# io-board-d-5.net
KiCad netlist of a schematic drawn in EAGLE
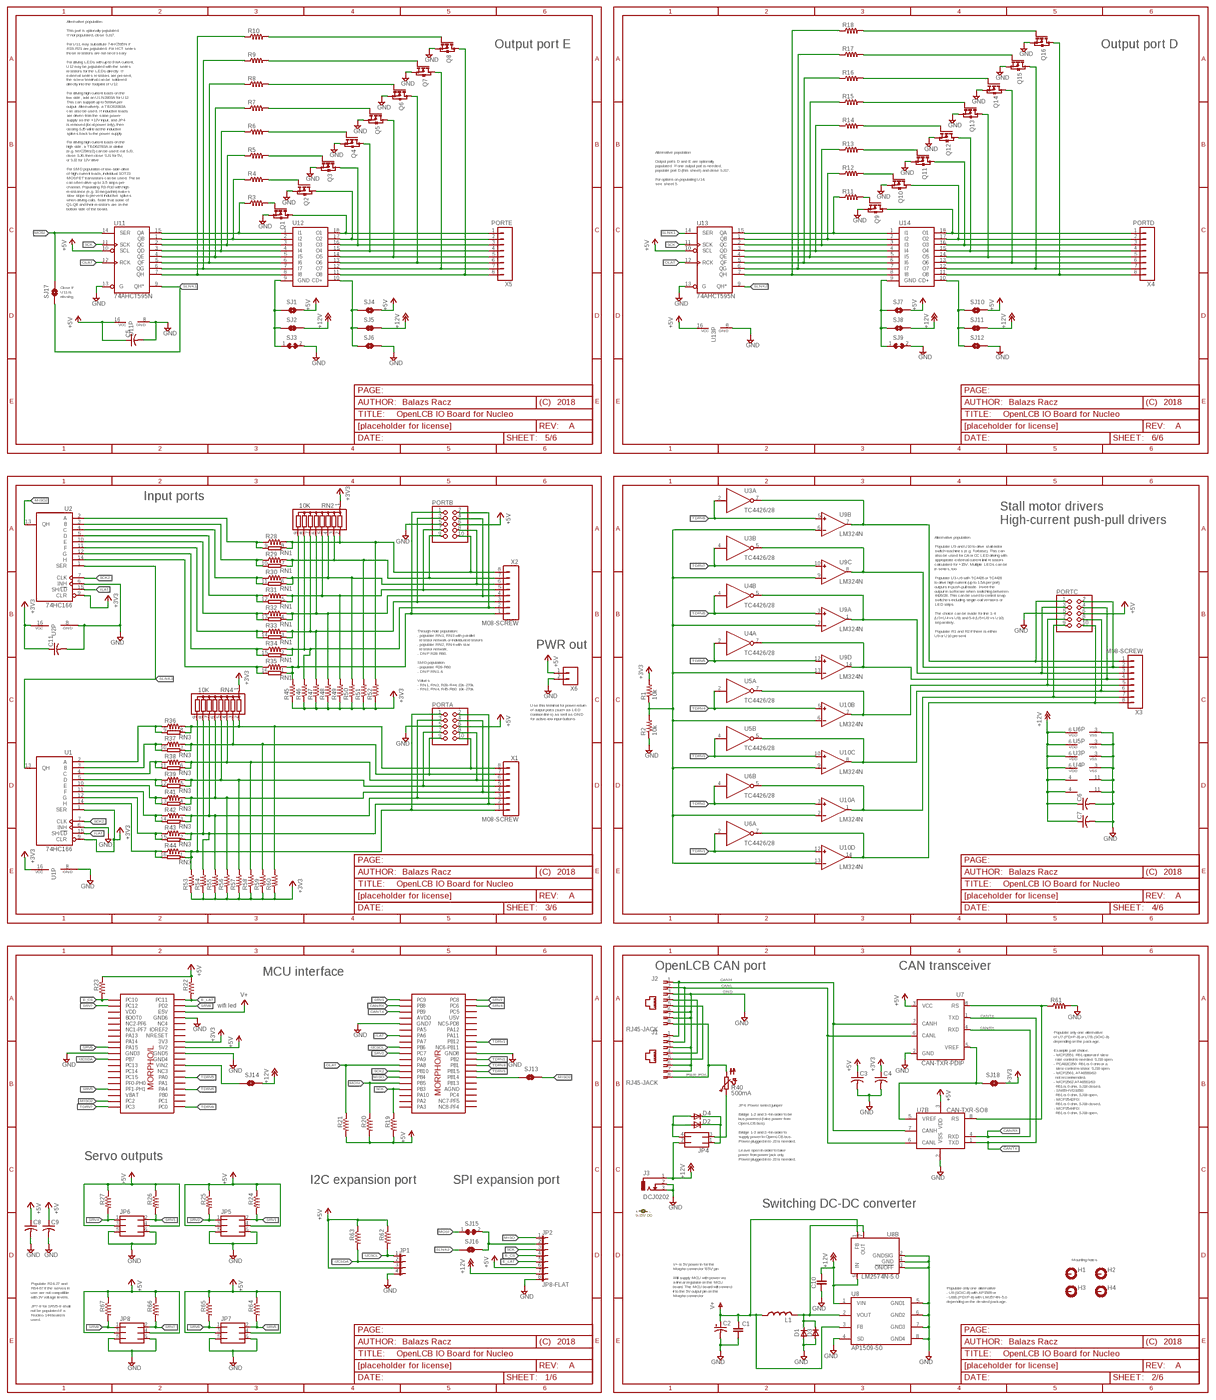
[diagram p0: schematic, sheet 1, overview]
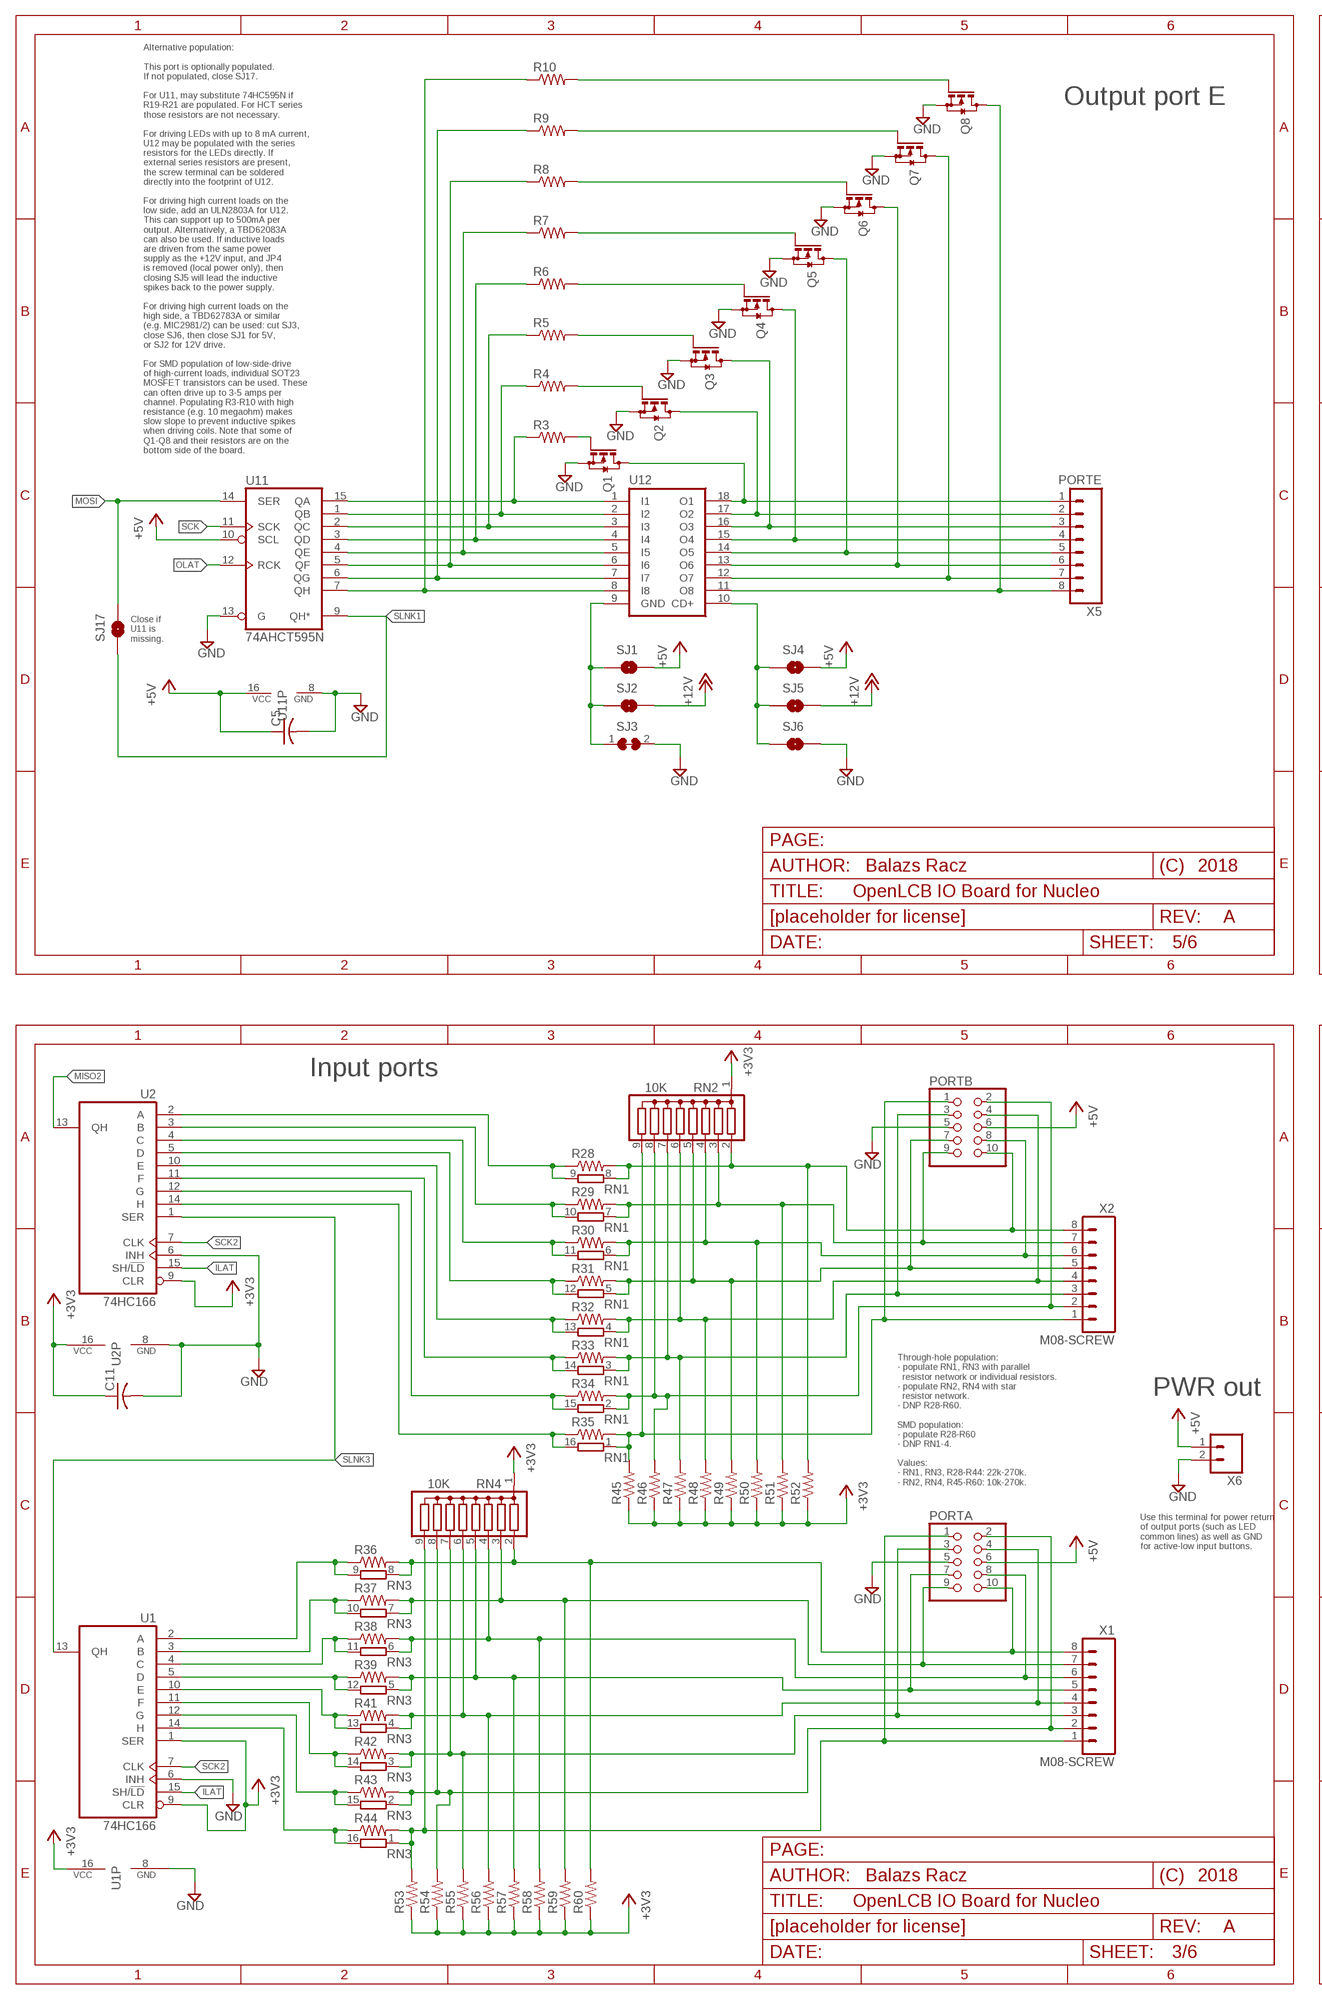
[diagram p1: schematic, sheet 1, part 1 of 4]
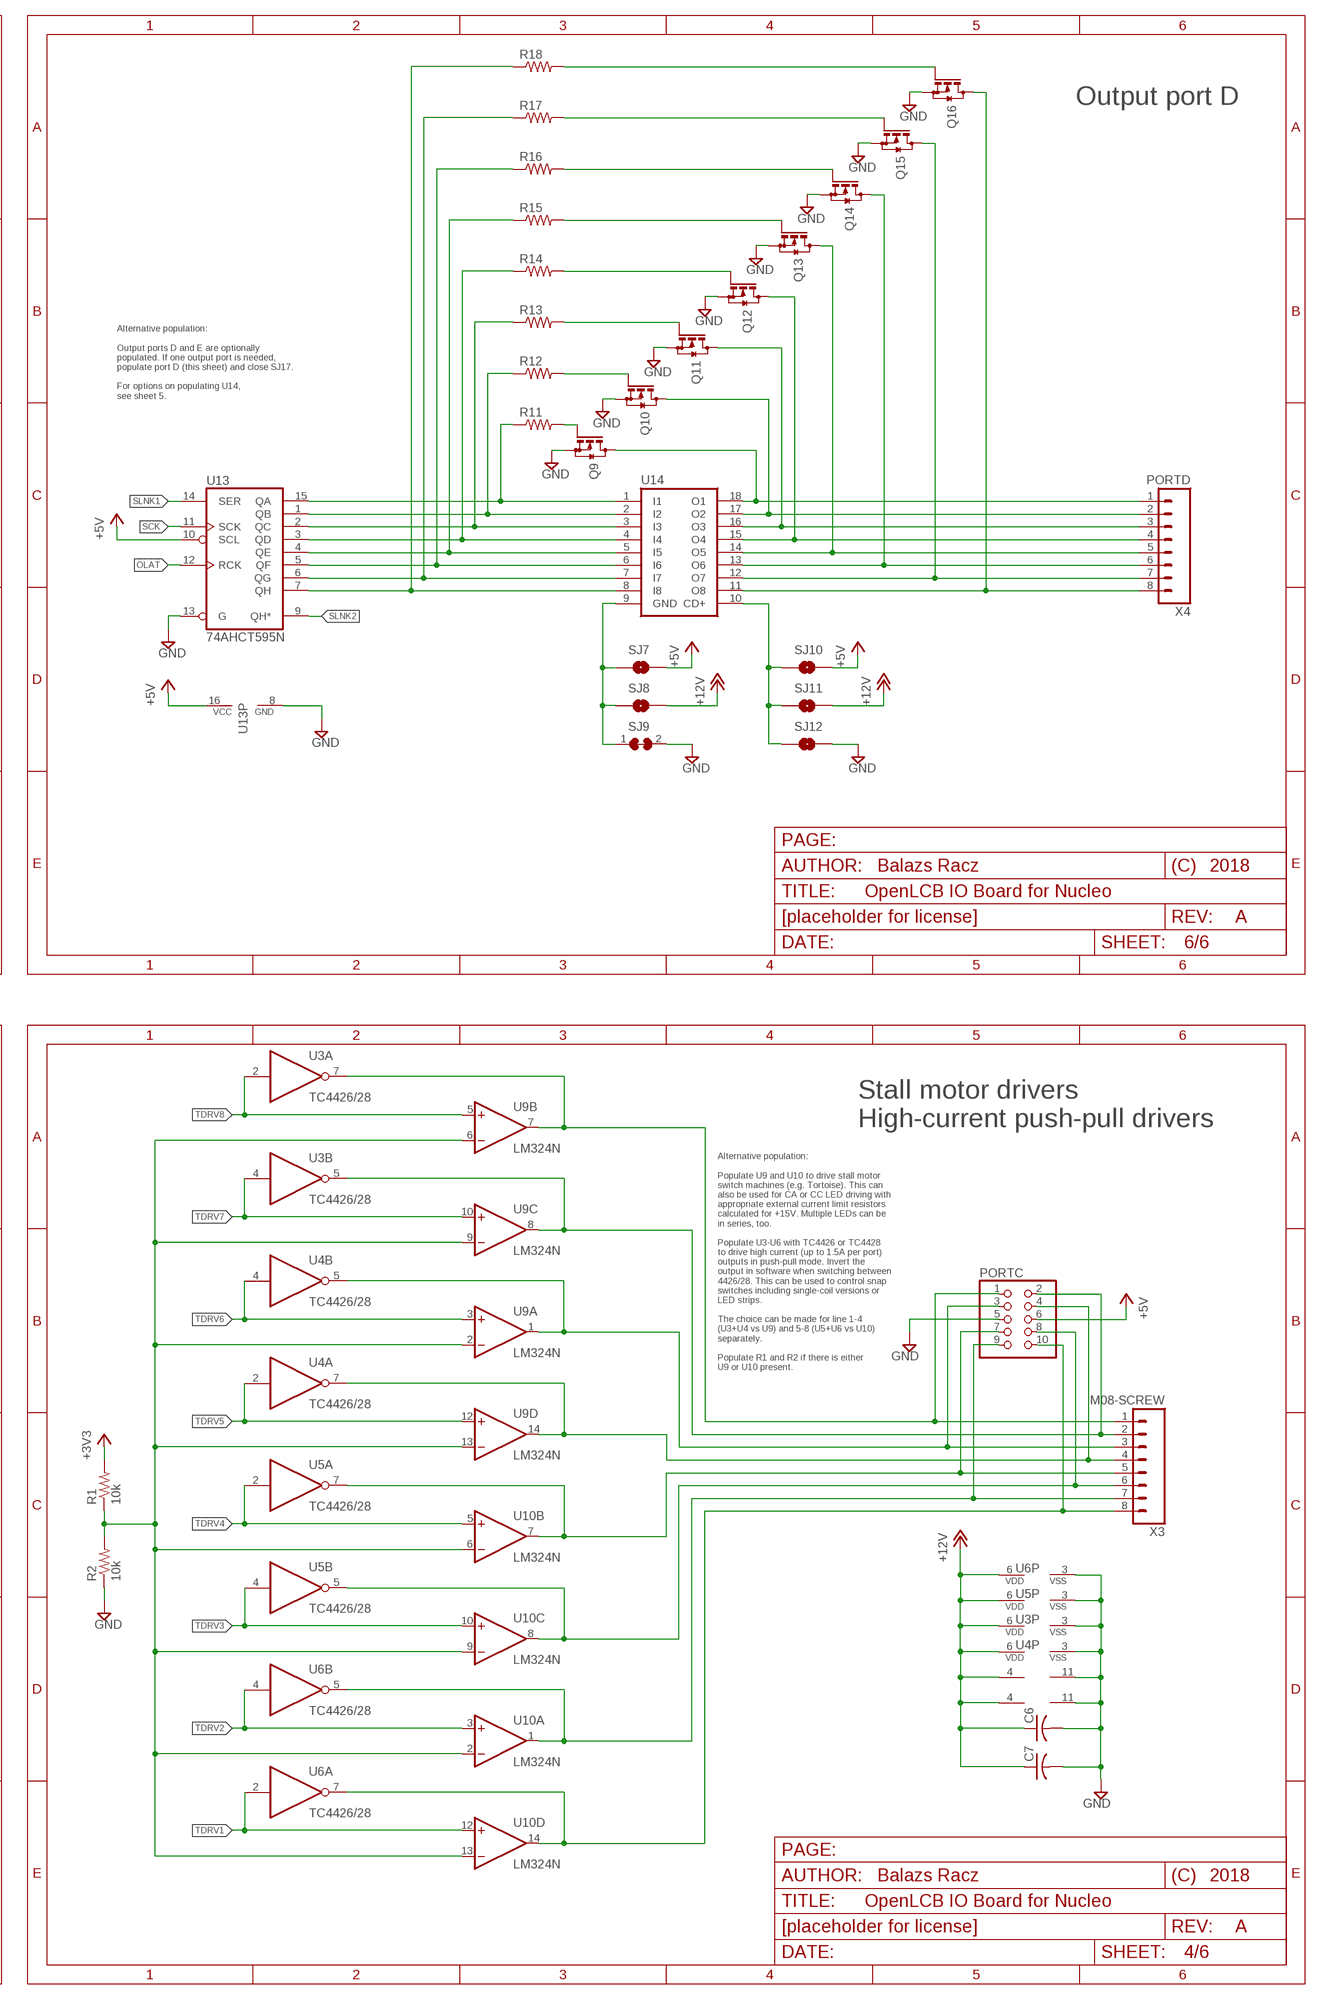
[diagram p2: schematic, sheet 1, part 2 of 4]
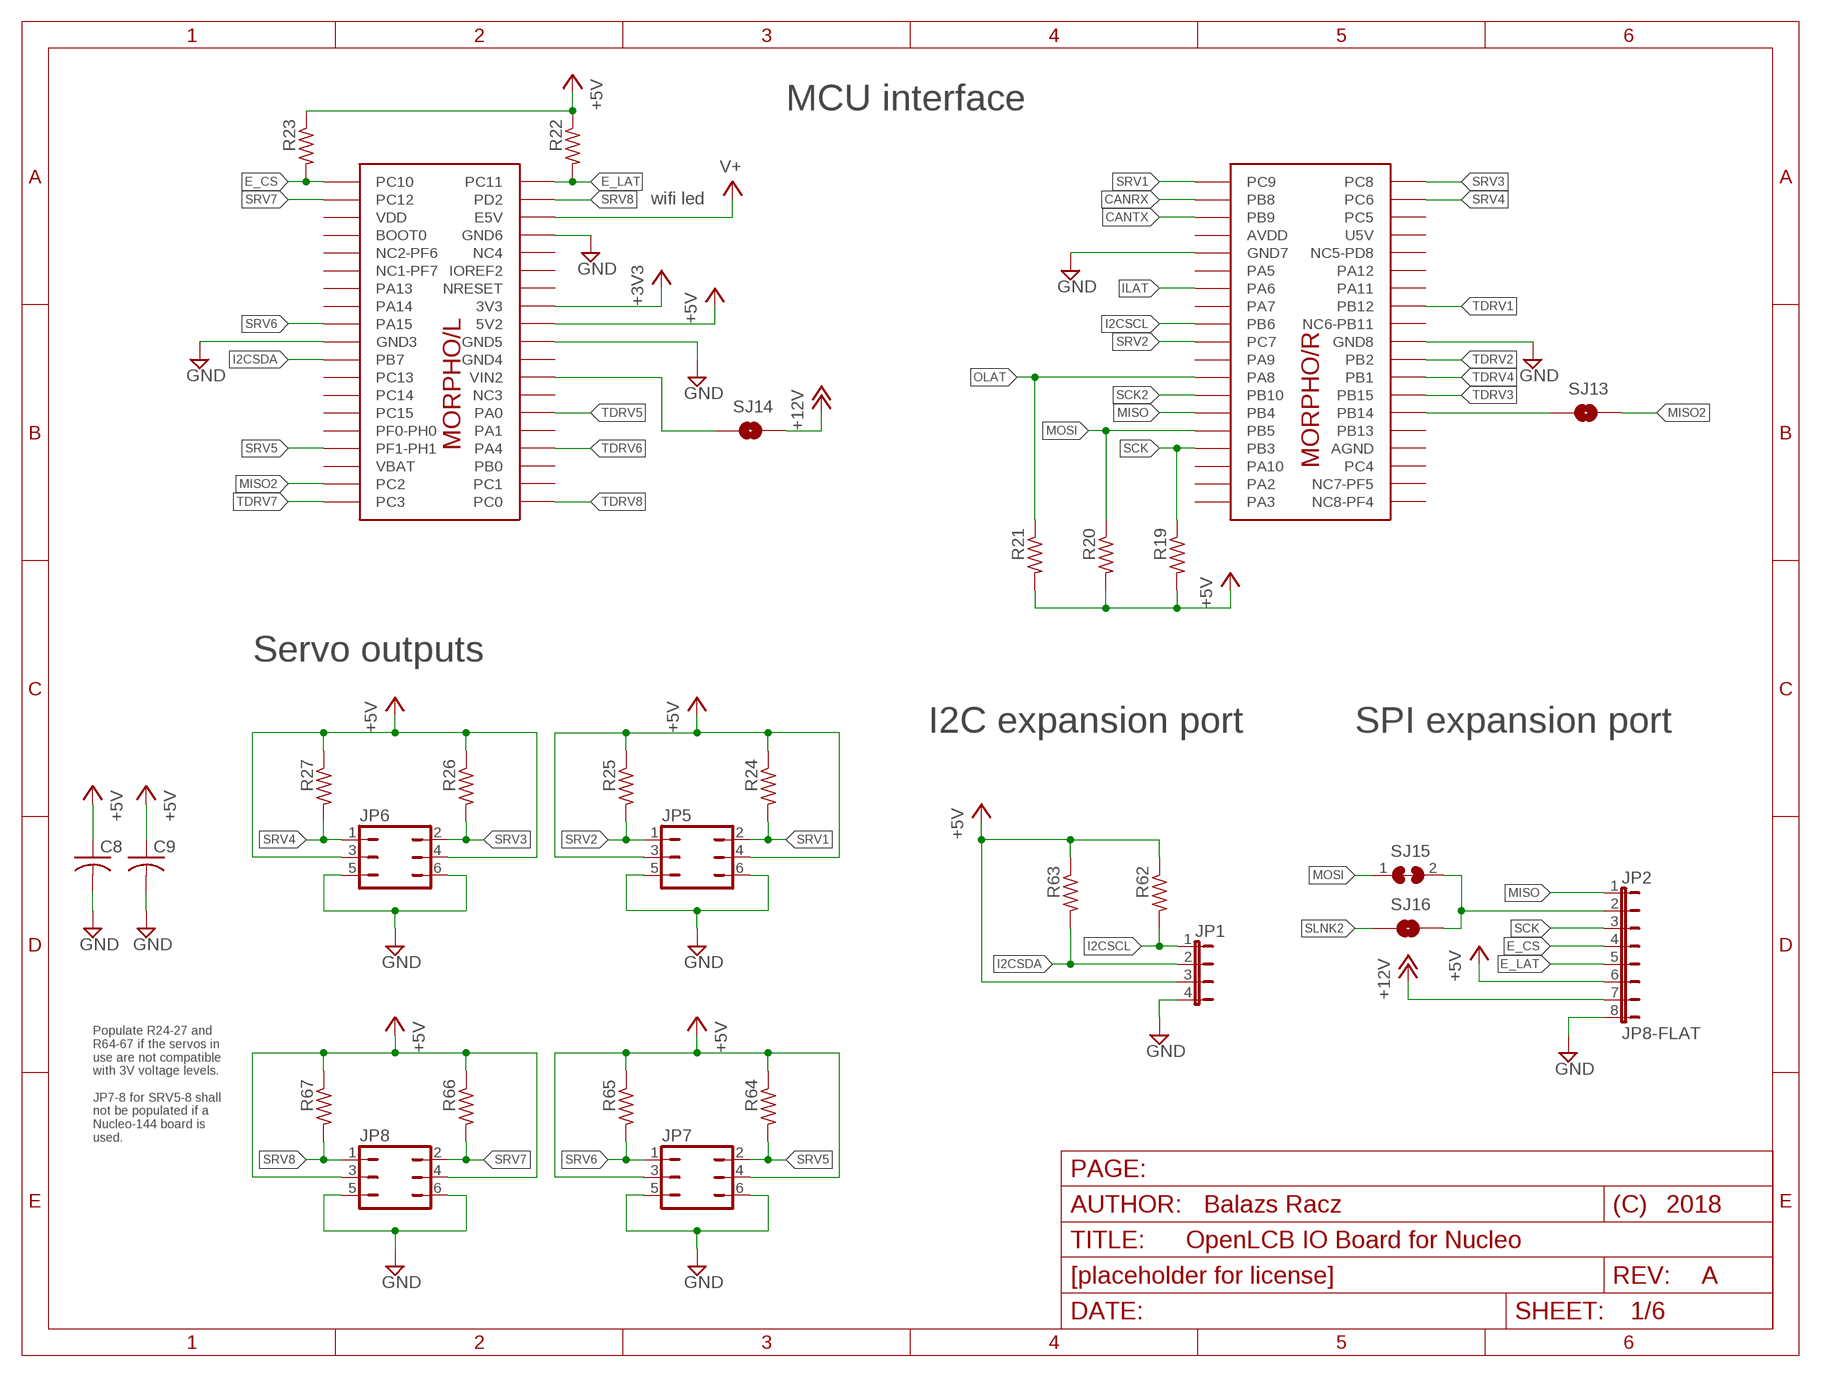
[diagram p3: schematic, sheet 1, part 3 of 4]
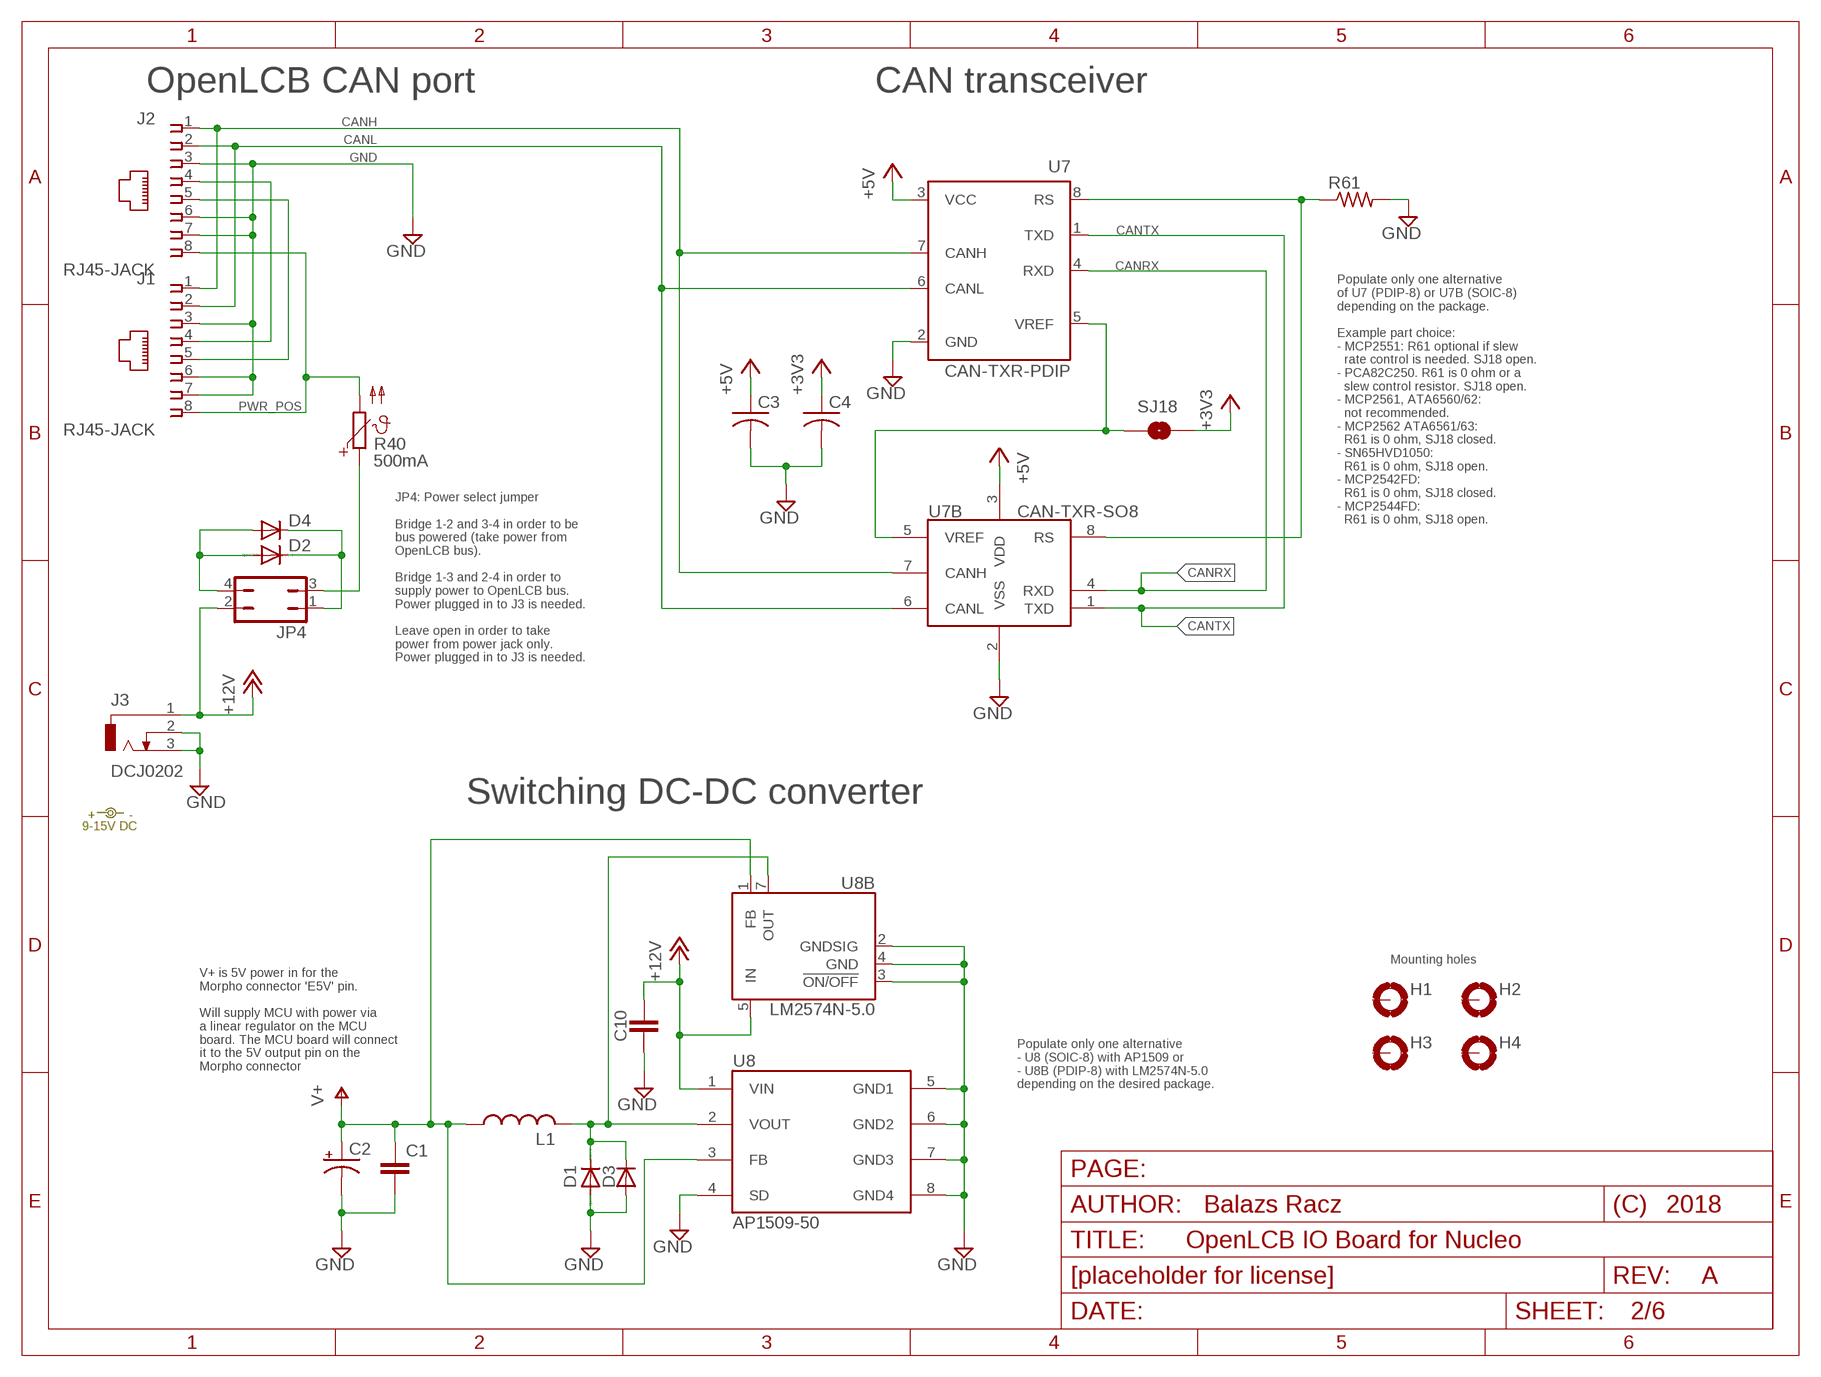
[diagram p4: schematic, sheet 1, part 4 of 4]

(export (version "E")
  (design (tool "Eeschema 10.0.6"))
  (components
    (comp (ref "+12V")
      (value "9-15V DC")
      (footprint "eagle-import:POWER_USAGE")
      (libsource (lib "eagle-import") (part "DOC-POWER_LABEL"))
    )
    (comp (ref "C1")
      (value "C-EUC1206")
      (footprint "eagle-import:C1206")
      (libsource (lib "eagle-import") (part "C-EUC1206"))
    )
    (comp (ref "C2")
      (value "CPOL-USE2.5-5")
      (footprint "eagle-import:E2,5-5")
      (libsource (lib "eagle-import") (part "CPOL-USE2.5-5"))
    )
    (comp (ref "C3")
      (value "C-USC0805")
      (footprint "eagle-import:C0805")
      (libsource (lib "eagle-import") (part "C-USC0805"))
    )
    (comp (ref "C4")
      (value "C-USC0805")
      (footprint "eagle-import:C0805")
      (libsource (lib "eagle-import") (part "C-USC0805"))
    )
    (comp (ref "C5")
      (value "C-USC0805")
      (footprint "eagle-import:C0805")
      (libsource (lib "eagle-import") (part "C-USC0805"))
    )
    (comp (ref "C6")
      (value "C-USC1206")
      (footprint "eagle-import:C1206")
      (libsource (lib "eagle-import") (part "C-USC1206"))
    )
    (comp (ref "C7")
      (value "C-USC1206")
      (footprint "eagle-import:C1206")
      (libsource (lib "eagle-import") (part "C-USC1206"))
    )
    (comp (ref "C8")
      (value "C-USC1206")
      (footprint "eagle-import:C1206")
      (libsource (lib "eagle-import") (part "C-USC1206"))
    )
    (comp (ref "C9")
      (value "C-USC1206")
      (footprint "eagle-import:C1206")
      (libsource (lib "eagle-import") (part "C-USC1206"))
    )
    (comp (ref "C10")
      (value "C-EUC1206")
      (footprint "eagle-import:C1206")
      (libsource (lib "eagle-import") (part "C-EUC1206"))
    )
    (comp (ref "C11")
      (value "C-USC0805")
      (footprint "eagle-import:C0805")
      (libsource (lib "eagle-import") (part "C-USC0805"))
    )
    (comp (ref "D1")
      (value "DIODE-DO41-7.6")
      (footprint "eagle-import:DO41-7.6")
      (libsource (lib "eagle-import") (part "DIODE-DO41-7.6"))
    )
    (comp (ref "D2")
      (value "DIODE-DO41-7.6")
      (footprint "eagle-import:DO41-7.6")
      (libsource (lib "eagle-import") (part "DIODE-DO41-7.6"))
    )
    (comp (ref "D3")
      (value "DIODEDO-214AA-NODOC")
      (footprint "eagle-import:DO214AA-NODOC")
      (libsource (lib "eagle-import") (part "DIODEDO-214AA-NODOC"))
    )
    (comp (ref "D4")
      (value "DIODEDO-214AA-NODOC")
      (footprint "eagle-import:DO214AA-NODOC")
      (libsource (lib "eagle-import") (part "DIODEDO-214AA-NODOC"))
    )
    (comp (ref "H1")
      (value "MOUNT-PAD-ROUND3.3")
      (footprint "eagle-import:3,3-PAD")
      (libsource (lib "eagle-import") (part "MOUNT-PAD-ROUND3.3"))
    )
    (comp (ref "H2")
      (value "MOUNT-PAD-ROUND3.3")
      (footprint "eagle-import:3,3-PAD")
      (libsource (lib "eagle-import") (part "MOUNT-PAD-ROUND3.3"))
    )
    (comp (ref "H3")
      (value "MOUNT-PAD-ROUND3.3")
      (footprint "eagle-import:3,3-PAD")
      (libsource (lib "eagle-import") (part "MOUNT-PAD-ROUND3.3"))
    )
    (comp (ref "H4")
      (value "MOUNT-PAD-ROUND3.3")
      (footprint "eagle-import:3,3-PAD")
      (libsource (lib "eagle-import") (part "MOUNT-PAD-ROUND3.3"))
    )
    (comp (ref "J1")
      (value "RJ45-JACK")
      (footprint "eagle-import:RJ45-PULSE-E5J88")
      (libsource (lib "eagle-import") (part "RJ45-JACKRJ45-PULSE-E5J00"))
    )
    (comp (ref "J2")
      (value "RJ45-JACK")
      (footprint "eagle-import:RJ45-PULSE-E5J88")
      (libsource (lib "eagle-import") (part "RJ45-JACKRJ45-PULSE-E5J00"))
    )
    (comp (ref "J3")
      (value "DCJ0202")
      (footprint "eagle-import:DCJ0202")
      (libsource (lib "eagle-import") (part "DCJ0202"))
    )
    (comp (ref "JP1")
      (value "JP4-FLAT")
      (footprint "eagle-import:JP4F")
      (libsource (lib "eagle-import") (part "JP4-FLAT"))
    )
    (comp (ref "JP2")
      (value "JP8-FLAT")
      (footprint "eagle-import:JP8F")
      (libsource (lib "eagle-import") (part "JP8-FLAT"))
    )
    (comp (ref "JP4")
      (value "JP2Q")
      (footprint "eagle-import:JP2Q")
      (libsource (lib "eagle-import") (part "JP2Q"))
    )
    (comp (ref "JP5")
      (value "JP3Q")
      (footprint "eagle-import:JP3Q")
      (libsource (lib "eagle-import") (part "JP3Q"))
    )
    (comp (ref "JP6")
      (value "JP3Q")
      (footprint "eagle-import:JP3Q")
      (libsource (lib "eagle-import") (part "JP3Q"))
    )
    (comp (ref "JP7")
      (value "JP3Q")
      (footprint "eagle-import:JP3Q")
      (libsource (lib "eagle-import") (part "JP3Q"))
    )
    (comp (ref "JP8")
      (value "JP3Q")
      (footprint "eagle-import:JP3Q")
      (libsource (lib "eagle-import") (part "JP3Q"))
    )
    (comp (ref "L1")
      (value "L-US")
      (footprint "eagle-import:L5-8,5")
      (libsource (lib "eagle-import") (part "L-US"))
    )
    (comp (ref "PORTA")
      (value "PINHD-2X5CN")
      (footprint "eagle-import:CON10M")
      (libsource (lib "eagle-import") (part "PINHD-2X5CN"))
    )
    (comp (ref "PORTB")
      (value "PINHD-2X5CN")
      (footprint "eagle-import:CON10M")
      (libsource (lib "eagle-import") (part "PINHD-2X5CN"))
    )
    (comp (ref "PORTC")
      (value "PINHD-2X5CN")
      (footprint "eagle-import:CON10M")
      (libsource (lib "eagle-import") (part "PINHD-2X5CN"))
    )
    (comp (ref "Q1")
      (value "BSS123")
      (footprint "eagle-import:SOT23")
      (libsource (lib "eagle-import") (part "BSS123"))
    )
    (comp (ref "Q2")
      (value "BSS123")
      (footprint "eagle-import:SOT23")
      (libsource (lib "eagle-import") (part "BSS123"))
    )
    (comp (ref "Q3")
      (value "BSS123")
      (footprint "eagle-import:SOT23")
      (libsource (lib "eagle-import") (part "BSS123"))
    )
    (comp (ref "Q4")
      (value "BSS123")
      (footprint "eagle-import:SOT23")
      (libsource (lib "eagle-import") (part "BSS123"))
    )
    (comp (ref "Q5")
      (value "BSS123")
      (footprint "eagle-import:SOT23")
      (libsource (lib "eagle-import") (part "BSS123"))
    )
    (comp (ref "Q6")
      (value "BSS123")
      (footprint "eagle-import:SOT23")
      (libsource (lib "eagle-import") (part "BSS123"))
    )
    (comp (ref "Q7")
      (value "BSS123")
      (footprint "eagle-import:SOT23")
      (libsource (lib "eagle-import") (part "BSS123"))
    )
    (comp (ref "Q8")
      (value "BSS123")
      (footprint "eagle-import:SOT23")
      (libsource (lib "eagle-import") (part "BSS123"))
    )
    (comp (ref "Q9")
      (value "BSS123")
      (footprint "eagle-import:SOT23")
      (libsource (lib "eagle-import") (part "BSS123"))
    )
    (comp (ref "Q10")
      (value "BSS123")
      (footprint "eagle-import:SOT23")
      (libsource (lib "eagle-import") (part "BSS123"))
    )
    (comp (ref "Q11")
      (value "BSS123")
      (footprint "eagle-import:SOT23")
      (libsource (lib "eagle-import") (part "BSS123"))
    )
    (comp (ref "Q12")
      (value "BSS123")
      (footprint "eagle-import:SOT23")
      (libsource (lib "eagle-import") (part "BSS123"))
    )
    (comp (ref "Q13")
      (value "BSS123")
      (footprint "eagle-import:SOT23")
      (libsource (lib "eagle-import") (part "BSS123"))
    )
    (comp (ref "Q14")
      (value "BSS123")
      (footprint "eagle-import:SOT23")
      (libsource (lib "eagle-import") (part "BSS123"))
    )
    (comp (ref "Q15")
      (value "BSS123")
      (footprint "eagle-import:SOT23")
      (libsource (lib "eagle-import") (part "BSS123"))
    )
    (comp (ref "Q16")
      (value "BSS123")
      (footprint "eagle-import:SOT23")
      (libsource (lib "eagle-import") (part "BSS123"))
    )
    (comp (ref "R1")
      (value "10k")
      (footprint "eagle-import:R0805")
      (libsource (lib "eagle-import") (part "R-US_R0805"))
    )
    (comp (ref "R2")
      (value "10k")
      (footprint "eagle-import:R0805")
      (libsource (lib "eagle-import") (part "R-US_R0805"))
    )
    (comp (ref "R3")
      (value "R-US_R0603")
      (footprint "eagle-import:R0603")
      (libsource (lib "eagle-import") (part "R-US_R0603"))
    )
    (comp (ref "R4")
      (value "R-US_R0603")
      (footprint "eagle-import:R0603")
      (libsource (lib "eagle-import") (part "R-US_R0603"))
    )
    (comp (ref "R5")
      (value "R-US_R0603")
      (footprint "eagle-import:R0603")
      (libsource (lib "eagle-import") (part "R-US_R0603"))
    )
    (comp (ref "R6")
      (value "R-US_R0603")
      (footprint "eagle-import:R0603")
      (libsource (lib "eagle-import") (part "R-US_R0603"))
    )
    (comp (ref "R7")
      (value "R-US_R0603")
      (footprint "eagle-import:R0603")
      (libsource (lib "eagle-import") (part "R-US_R0603"))
    )
    (comp (ref "R8")
      (value "R-US_R0603")
      (footprint "eagle-import:R0603")
      (libsource (lib "eagle-import") (part "R-US_R0603"))
    )
    (comp (ref "R9")
      (value "R-US_R0603")
      (footprint "eagle-import:R0603")
      (libsource (lib "eagle-import") (part "R-US_R0603"))
    )
    (comp (ref "R10")
      (value "R-US_R0603")
      (footprint "eagle-import:R0603")
      (libsource (lib "eagle-import") (part "R-US_R0603"))
    )
    (comp (ref "R11")
      (value "R-US_R0603")
      (footprint "eagle-import:R0603")
      (libsource (lib "eagle-import") (part "R-US_R0603"))
    )
    (comp (ref "R12")
      (value "R-US_R0603")
      (footprint "eagle-import:R0603")
      (libsource (lib "eagle-import") (part "R-US_R0603"))
    )
    (comp (ref "R13")
      (value "R-US_R0603")
      (footprint "eagle-import:R0603")
      (libsource (lib "eagle-import") (part "R-US_R0603"))
    )
    (comp (ref "R14")
      (value "R-US_R0603")
      (footprint "eagle-import:R0603")
      (libsource (lib "eagle-import") (part "R-US_R0603"))
    )
    (comp (ref "R15")
      (value "R-US_R0603")
      (footprint "eagle-import:R0603")
      (libsource (lib "eagle-import") (part "R-US_R0603"))
    )
    (comp (ref "R16")
      (value "R-US_R0603")
      (footprint "eagle-import:R0603")
      (libsource (lib "eagle-import") (part "R-US_R0603"))
    )
    (comp (ref "R17")
      (value "R-US_R0603")
      (footprint "eagle-import:R0603")
      (libsource (lib "eagle-import") (part "R-US_R0603"))
    )
    (comp (ref "R18")
      (value "R-US_R0603")
      (footprint "eagle-import:R0603")
      (libsource (lib "eagle-import") (part "R-US_R0603"))
    )
    (comp (ref "R19")
      (value "R-US_R0805")
      (footprint "eagle-import:R0805")
      (libsource (lib "eagle-import") (part "rcl_334_R-US_R0805"))
    )
    (comp (ref "R20")
      (value "R-US_R0805")
      (footprint "eagle-import:R0805")
      (libsource (lib "eagle-import") (part "rcl_334_R-US_R0805"))
    )
    (comp (ref "R21")
      (value "R-US_R0805")
      (footprint "eagle-import:R0805")
      (libsource (lib "eagle-import") (part "rcl_334_R-US_R0805"))
    )
    (comp (ref "R22")
      (value "R-US_R0805")
      (footprint "eagle-import:R0805")
      (libsource (lib "eagle-import") (part "rcl_334_R-US_R0805"))
    )
    (comp (ref "R23")
      (value "R-US_R0805")
      (footprint "eagle-import:R0805")
      (libsource (lib "eagle-import") (part "rcl_334_R-US_R0805"))
    )
    (comp (ref "R24")
      (value "R-US_R0805")
      (footprint "eagle-import:R0805")
      (libsource (lib "eagle-import") (part "rcl_334_R-US_R0805"))
    )
    (comp (ref "R25")
      (value "R-US_R0805")
      (footprint "eagle-import:R0805")
      (libsource (lib "eagle-import") (part "rcl_334_R-US_R0805"))
    )
    (comp (ref "R26")
      (value "R-US_R0805")
      (footprint "eagle-import:R0805")
      (libsource (lib "eagle-import") (part "rcl_334_R-US_R0805"))
    )
    (comp (ref "R27")
      (value "R-US_R0805")
      (footprint "eagle-import:R0805")
      (libsource (lib "eagle-import") (part "rcl_334_R-US_R0805"))
    )
    (comp (ref "R28")
      (value "R-US_R0603")
      (footprint "eagle-import:R0603")
      (libsource (lib "eagle-import") (part "rcl_334_R-US_R0603"))
    )
    (comp (ref "R29")
      (value "R-US_R0603")
      (footprint "eagle-import:R0603")
      (libsource (lib "eagle-import") (part "rcl_334_R-US_R0603"))
    )
    (comp (ref "R30")
      (value "R-US_R0603")
      (footprint "eagle-import:R0603")
      (libsource (lib "eagle-import") (part "rcl_334_R-US_R0603"))
    )
    (comp (ref "R31")
      (value "R-US_R0603")
      (footprint "eagle-import:R0603")
      (libsource (lib "eagle-import") (part "rcl_334_R-US_R0603"))
    )
    (comp (ref "R32")
      (value "R-US_R0603")
      (footprint "eagle-import:R0603")
      (libsource (lib "eagle-import") (part "rcl_334_R-US_R0603"))
    )
    (comp (ref "R33")
      (value "R-US_R0603")
      (footprint "eagle-import:R0603")
      (libsource (lib "eagle-import") (part "rcl_334_R-US_R0603"))
    )
    (comp (ref "R34")
      (value "R-US_R0603")
      (footprint "eagle-import:R0603")
      (libsource (lib "eagle-import") (part "rcl_334_R-US_R0603"))
    )
    (comp (ref "R35")
      (value "R-US_R0603")
      (footprint "eagle-import:R0603")
      (libsource (lib "eagle-import") (part "rcl_334_R-US_R0603"))
    )
    (comp (ref "R36")
      (value "R-US_R0603")
      (footprint "eagle-import:R0603")
      (libsource (lib "eagle-import") (part "rcl_334_R-US_R0603"))
    )
    (comp (ref "R37")
      (value "R-US_R0603")
      (footprint "eagle-import:R0603")
      (libsource (lib "eagle-import") (part "rcl_334_R-US_R0603"))
    )
    (comp (ref "R38")
      (value "R-US_R0603")
      (footprint "eagle-import:R0603")
      (libsource (lib "eagle-import") (part "rcl_334_R-US_R0603"))
    )
    (comp (ref "R39")
      (value "R-US_R0603")
      (footprint "eagle-import:R0603")
      (libsource (lib "eagle-import") (part "rcl_334_R-US_R0603"))
    )
    (comp (ref "R40")
      (value "500mA")
      (footprint "eagle-import:PTC1812")
      (libsource (lib "eagle-import") (part "PTC_1812"))
    )
    (comp (ref "R41")
      (value "R-US_R0603")
      (footprint "eagle-import:R0603")
      (libsource (lib "eagle-import") (part "rcl_334_R-US_R0603"))
    )
    (comp (ref "R42")
      (value "R-US_R0603")
      (footprint "eagle-import:R0603")
      (libsource (lib "eagle-import") (part "rcl_334_R-US_R0603"))
    )
    (comp (ref "R43")
      (value "R-US_R0603")
      (footprint "eagle-import:R0603")
      (libsource (lib "eagle-import") (part "rcl_334_R-US_R0603"))
    )
    (comp (ref "R44")
      (value "R-US_R0603")
      (footprint "eagle-import:R0603")
      (libsource (lib "eagle-import") (part "rcl_334_R-US_R0603"))
    )
    (comp (ref "R45")
      (value "R-US")
      (footprint "eagle-import:R0603")
      (libsource (lib "eagle-import") (part "R-US"))
    )
    (comp (ref "R46")
      (value "R-US")
      (footprint "eagle-import:R0603")
      (libsource (lib "eagle-import") (part "R-US"))
    )
    (comp (ref "R47")
      (value "R-US")
      (footprint "eagle-import:R0603")
      (libsource (lib "eagle-import") (part "R-US"))
    )
    (comp (ref "R48")
      (value "R-US")
      (footprint "eagle-import:R0603")
      (libsource (lib "eagle-import") (part "R-US"))
    )
    (comp (ref "R49")
      (value "R-US")
      (footprint "eagle-import:R0603")
      (libsource (lib "eagle-import") (part "R-US"))
    )
    (comp (ref "R50")
      (value "R-US")
      (footprint "eagle-import:R0603")
      (libsource (lib "eagle-import") (part "R-US"))
    )
    (comp (ref "R51")
      (value "R-US")
      (footprint "eagle-import:R0603")
      (libsource (lib "eagle-import") (part "R-US"))
    )
    (comp (ref "R52")
      (value "R-US")
      (footprint "eagle-import:R0603")
      (libsource (lib "eagle-import") (part "R-US"))
    )
    (comp (ref "R53")
      (value "R-US")
      (footprint "eagle-import:R0603")
      (libsource (lib "eagle-import") (part "R-US"))
    )
    (comp (ref "R54")
      (value "R-US")
      (footprint "eagle-import:R0603")
      (libsource (lib "eagle-import") (part "R-US"))
    )
    (comp (ref "R55")
      (value "R-US")
      (footprint "eagle-import:R0603")
      (libsource (lib "eagle-import") (part "R-US"))
    )
    (comp (ref "R56")
      (value "R-US")
      (footprint "eagle-import:R0603")
      (libsource (lib "eagle-import") (part "R-US"))
    )
    (comp (ref "R57")
      (value "R-US")
      (footprint "eagle-import:R0603")
      (libsource (lib "eagle-import") (part "R-US"))
    )
    (comp (ref "R58")
      (value "R-US")
      (footprint "eagle-import:R0603")
      (libsource (lib "eagle-import") (part "R-US"))
    )
    (comp (ref "R59")
      (value "R-US")
      (footprint "eagle-import:R0603")
      (libsource (lib "eagle-import") (part "R-US"))
    )
    (comp (ref "R60")
      (value "R-US")
      (footprint "eagle-import:R0603")
      (libsource (lib "eagle-import") (part "R-US"))
    )
    (comp (ref "R61")
      (value "R-US_R0805")
      (footprint "eagle-import:R0805")
      (libsource (lib "eagle-import") (part "rcl_334_R-US_R0805"))
    )
    (comp (ref "R62")
      (value "R-US_R0805")
      (footprint "eagle-import:R0805")
      (libsource (lib "eagle-import") (part "rcl_334_R-US_R0805"))
    )
    (comp (ref "R63")
      (value "R-US_R0805")
      (footprint "eagle-import:R0805")
      (libsource (lib "eagle-import") (part "rcl_334_R-US_R0805"))
    )
    (comp (ref "R64")
      (value "R-US_R0805")
      (footprint "eagle-import:R0805")
      (libsource (lib "eagle-import") (part "rcl_334_R-US_R0805"))
    )
    (comp (ref "R65")
      (value "R-US_R0805")
      (footprint "eagle-import:R0805")
      (libsource (lib "eagle-import") (part "rcl_334_R-US_R0805"))
    )
    (comp (ref "R66")
      (value "R-US_R0805")
      (footprint "eagle-import:R0805")
      (libsource (lib "eagle-import") (part "rcl_334_R-US_R0805"))
    )
    (comp (ref "R67")
      (value "R-US_R0805")
      (footprint "eagle-import:R0805")
      (libsource (lib "eagle-import") (part "rcl_334_R-US_R0805"))
    )
    (comp (ref "RN1")
      (value "8R-P")
      (footprint "eagle-import:DIL16")
      (libsource (lib "eagle-import") (part "8R-P"))
    )
    (comp (ref "RN2")
      (value "10K")
      (footprint "eagle-import:SIL9")
      (libsource (lib "eagle-import") (part "G08R"))
    )
    (comp (ref "RN3")
      (value "8R-P")
      (footprint "eagle-import:DIL16")
      (libsource (lib "eagle-import") (part "8R-P"))
    )
    (comp (ref "RN4")
      (value "10K")
      (footprint "eagle-import:SIL9")
      (libsource (lib "eagle-import") (part "G08R"))
    )
    (comp (ref "SJ1")
      (value "SJRND2")
      (footprint "eagle-import:SJ_RND2")
      (libsource (lib "eagle-import") (part "SJRND2"))
    )
    (comp (ref "SJ2")
      (value "SJRND2")
      (footprint "eagle-import:SJ_RND2")
      (libsource (lib "eagle-import") (part "SJRND2"))
    )
    (comp (ref "SJ3")
      (value "SJ-C")
      (footprint "eagle-import:SJW-C")
      (libsource (lib "eagle-import") (part "SJ-C"))
    )
    (comp (ref "SJ4")
      (value "SJRND2")
      (footprint "eagle-import:SJ_RND2")
      (libsource (lib "eagle-import") (part "SJRND2"))
    )
    (comp (ref "SJ5")
      (value "SJRND2")
      (footprint "eagle-import:SJ_RND2")
      (libsource (lib "eagle-import") (part "SJRND2"))
    )
    (comp (ref "SJ6")
      (value "SJRND2")
      (footprint "eagle-import:SJ_RND2")
      (libsource (lib "eagle-import") (part "SJRND2"))
    )
    (comp (ref "SJ7")
      (value "SJRND2")
      (footprint "eagle-import:SJ_RND2")
      (libsource (lib "eagle-import") (part "SJRND2"))
    )
    (comp (ref "SJ8")
      (value "SJRND2")
      (footprint "eagle-import:SJ_RND2")
      (libsource (lib "eagle-import") (part "SJRND2"))
    )
    (comp (ref "SJ9")
      (value "SJ-C")
      (footprint "eagle-import:SJW-C")
      (libsource (lib "eagle-import") (part "SJ-C"))
    )
    (comp (ref "SJ10")
      (value "SJRND2")
      (footprint "eagle-import:SJ_RND2")
      (libsource (lib "eagle-import") (part "SJRND2"))
    )
    (comp (ref "SJ11")
      (value "SJRND2")
      (footprint "eagle-import:SJ_RND2")
      (libsource (lib "eagle-import") (part "SJRND2"))
    )
    (comp (ref "SJ12")
      (value "SJRND2")
      (footprint "eagle-import:SJ_RND2")
      (libsource (lib "eagle-import") (part "SJRND2"))
    )
    (comp (ref "SJ13")
      (value "SJRND2")
      (footprint "eagle-import:SJ_RND2")
      (libsource (lib "eagle-import") (part "SJRND2"))
    )
    (comp (ref "SJ14")
      (value "SJRND2")
      (footprint "eagle-import:SJ_RND2")
      (libsource (lib "eagle-import") (part "SJRND2"))
    )
    (comp (ref "SJ15")
      (value "SJ-C")
      (footprint "eagle-import:SJW-C")
      (libsource (lib "eagle-import") (part "SJ-C"))
    )
    (comp (ref "SJ16")
      (value "SJRND2")
      (footprint "eagle-import:SJ_RND2")
      (libsource (lib "eagle-import") (part "SJRND2"))
    )
    (comp (ref "SJ17")
      (value "SJRND2")
      (footprint "eagle-import:SJ_RND2")
      (libsource (lib "eagle-import") (part "SJRND2"))
    )
    (comp (ref "SJ18")
      (value "SJRND2")
      (footprint "eagle-import:SJ_RND2")
      (libsource (lib "eagle-import") (part "SJRND2"))
    )
    (comp (ref "U$1")
      (value "NUCLEO_64_GENERIC")
      (footprint "eagle-import:NUCLEO_BRD_BASE64")
      (libsource (lib "eagle-import") (part "NUCLEO_64_GENERIC"))
    )
    (comp (ref "U1")
      (value "74HC166")
      (footprint "eagle-import:DIL16")
      (libsource (lib "eagle-import") (part "74166N"))
    )
    (comp (ref "U2")
      (value "74HC166")
      (footprint "eagle-import:DIL16")
      (libsource (lib "eagle-import") (part "74166N"))
    )
    (comp (ref "U3")
      (value "TC4426/28")
      (footprint "eagle-import:DIL08-LONG")
      (libsource (lib "eagle-import") (part "TC4426APDIP"))
    )
    (comp (ref "U4")
      (value "TC4426/28")
      (footprint "eagle-import:DIL08-LONG")
      (libsource (lib "eagle-import") (part "TC4426APDIP"))
    )
    (comp (ref "U5")
      (value "TC4426/28")
      (footprint "eagle-import:DIL08-LONG")
      (libsource (lib "eagle-import") (part "TC4426APDIP"))
    )
    (comp (ref "U6")
      (value "TC4426/28")
      (footprint "eagle-import:DIL08-LONG")
      (libsource (lib "eagle-import") (part "TC4426APDIP"))
    )
    (comp (ref "U7")
      (value "CAN-TXR-PDIP")
      (footprint "eagle-import:DIL08")
      (libsource (lib "eagle-import") (part "PCA82C250"))
    )
    (comp (ref "U7B")
      (value "CAN-TXR-SO8")
      (footprint "eagle-import:SO-08")
      (libsource (lib "eagle-import") (part "MCP2551-SN"))
    )
    (comp (ref "U8")
      (value "AP1509-50")
      (footprint "eagle-import:SO-08")
      (libsource (lib "eagle-import") (part "AP1509"))
    )
    (comp (ref "U8B")
      (value "LM2574N-5.0")
      (footprint "eagle-import:DIL08")
      (libsource (lib "eagle-import") (part "LM2574?-N5.0"))
    )
    (comp (ref "U9")
      (value "LM324N")
      (footprint "eagle-import:DIL14")
      (libsource (lib "eagle-import") (part "LM324N"))
    )
    (comp (ref "U10")
      (value "LM324N")
      (footprint "eagle-import:DIL14")
      (libsource (lib "eagle-import") (part "LM324N"))
    )
    (comp (ref "U11")
      (value "74AHCT595N")
      (footprint "eagle-import:DIL16")
      (libsource (lib "eagle-import") (part "74595NHCT"))
    )
    (comp (ref "U12")
      (value "ULN2803A")
      (footprint "eagle-import:DIL18-THIN")
      (libsource (lib "eagle-import") (part "ULN2803A"))
    )
    (comp (ref "U13")
      (value "74AHCT595N")
      (footprint "eagle-import:DIL16")
      (libsource (lib "eagle-import") (part "74595NHCT"))
    )
    (comp (ref "U14")
      (value "ULN2803A")
      (footprint "eagle-import:DIL18-THIN")
      (libsource (lib "eagle-import") (part "ULN2803A"))
    )
    (comp (ref "X1")
      (value "M08-SCREW")
      (footprint "eagle-import:1X08_TERMINAL")
      (libsource (lib "eagle-import") (part "M08-SCREW"))
    )
    (comp (ref "X2")
      (value "M08-SCREW")
      (footprint "eagle-import:1X08_TERMINAL")
      (libsource (lib "eagle-import") (part "M08-SCREW"))
    )
    (comp (ref "X3")
      (value "M08-SCREW")
      (footprint "eagle-import:1X08_TERMINAL")
      (libsource (lib "eagle-import") (part "M08-SCREW"))
    )
    (comp (ref "X4")
      (value "PORTD")
      (footprint "eagle-import:1X08_TERMINAL")
      (libsource (lib "eagle-import") (part "M08-SCREW"))
    )
    (comp (ref "X5")
      (value "PORTE")
      (footprint "eagle-import:1X08_TERMINAL")
      (libsource (lib "eagle-import") (part "M08-SCREW"))
    )
    (comp (ref "X6")
      (value "CONNECTOR-M023.5MM-LOCK")
      (footprint "eagle-import:SCREWTERMINAL-3.5MM-2_LOCK")
      (libsource (lib "eagle-import") (part "CONNECTOR-M023.5MM-LOCK"))
    )
  )
  (nets
    (net (code "1") (name "+3V3") (class "Default")
      (node (ref "C11") (pin "1") (pinfunction "1_1") (pintype "passive"))
      (node (ref "C4") (pin "1") (pinfunction "1_1") (pintype "passive"))
      (node (ref "R1") (pin "2") (pinfunction "2_2") (pintype "passive"))
      (node (ref "R45") (pin "1") (pinfunction "1_1") (pintype "passive"))
      (node (ref "R46") (pin "1") (pinfunction "1_1") (pintype "passive"))
      (node (ref "R47") (pin "1") (pinfunction "1_1") (pintype "passive"))
      (node (ref "R48") (pin "1") (pinfunction "1_1") (pintype "passive"))
      (node (ref "R49") (pin "1") (pinfunction "1_1") (pintype "passive"))
      (node (ref "R50") (pin "1") (pinfunction "1_1") (pintype "passive"))
      (node (ref "R51") (pin "1") (pinfunction "1_1") (pintype "passive"))
      (node (ref "R52") (pin "1") (pinfunction "1_1") (pintype "passive"))
      (node (ref "R53") (pin "1") (pinfunction "1_1") (pintype "passive"))
      (node (ref "R54") (pin "1") (pinfunction "1_1") (pintype "passive"))
      (node (ref "R55") (pin "1") (pinfunction "1_1") (pintype "passive"))
      (node (ref "R56") (pin "1") (pinfunction "1_1") (pintype "passive"))
      (node (ref "R57") (pin "1") (pinfunction "1_1") (pintype "passive"))
      (node (ref "R58") (pin "1") (pinfunction "1_1") (pintype "passive"))
      (node (ref "R59") (pin "1") (pinfunction "1_1") (pintype "passive"))
      (node (ref "R60") (pin "1") (pinfunction "1_1") (pintype "passive"))
      (node (ref "RN2") (pin "1") (pinfunction "1_1") (pintype "passive"))
      (node (ref "RN4") (pin "1") (pinfunction "1_1") (pintype "passive"))
      (node (ref "SJ18") (pin "P$1") (pinfunction "1_P$1") (pintype "passive"))
      (node (ref "U$1") (pin "3V3") (pinfunction "3V3_3V3") (pintype "power_in"))
      (node (ref "U1") (pin "1") (pinfunction "SER_1") (pintype "input"))
      (node (ref "U1") (pin "16") (pinfunction "VCC_16") (pintype "power_in"))
      (node (ref "U1") (pin "9") (pinfunction "CLR_9") (pintype "input"))
      (node (ref "U2") (pin "16") (pinfunction "VCC_16") (pintype "power_in"))
      (node (ref "U2") (pin "9") (pinfunction "CLR_9") (pintype "input"))
    )
    (net (code "2") (name "+5V") (class "Default")
      (node (ref "C3") (pin "1") (pinfunction "1_1") (pintype "passive"))
      (node (ref "C5") (pin "1") (pinfunction "1_1") (pintype "passive"))
      (node (ref "C8") (pin "1") (pinfunction "1_1") (pintype "passive"))
      (node (ref "C9") (pin "1") (pinfunction "1_1") (pintype "passive"))
      (node (ref "JP1") (pin "3") (pinfunction "3_3") (pintype "passive"))
      (node (ref "JP2") (pin "6") (pinfunction "6_6") (pintype "passive"))
      (node (ref "JP5") (pin "3") (pinfunction "3_3") (pintype "passive"))
      (node (ref "JP5") (pin "4") (pinfunction "4_4") (pintype "passive"))
      (node (ref "JP6") (pin "3") (pinfunction "3_3") (pintype "passive"))
      (node (ref "JP6") (pin "4") (pinfunction "4_4") (pintype "passive"))
      (node (ref "JP7") (pin "3") (pinfunction "3_3") (pintype "passive"))
      (node (ref "JP7") (pin "4") (pinfunction "4_4") (pintype "passive"))
      (node (ref "JP8") (pin "3") (pinfunction "3_3") (pintype "passive"))
      (node (ref "JP8") (pin "4") (pinfunction "4_4") (pintype "passive"))
      (node (ref "PORTA") (pin "6") (pinfunction "6_6") (pintype "passive"))
      (node (ref "PORTB") (pin "6") (pinfunction "6_6") (pintype "passive"))
      (node (ref "PORTC") (pin "6") (pinfunction "6_6") (pintype "passive"))
      (node (ref "R19") (pin "2") (pinfunction "2_2") (pintype "passive"))
      (node (ref "R20") (pin "2") (pinfunction "2_2") (pintype "passive"))
      (node (ref "R21") (pin "2") (pinfunction "2_2") (pintype "passive"))
      (node (ref "R22") (pin "1") (pinfunction "1_1") (pintype "passive"))
      (node (ref "R23") (pin "1") (pinfunction "1_1") (pintype "passive"))
      (node (ref "R24") (pin "1") (pinfunction "1_1") (pintype "passive"))
      (node (ref "R25") (pin "1") (pinfunction "1_1") (pintype "passive"))
      (node (ref "R26") (pin "1") (pinfunction "1_1") (pintype "passive"))
      (node (ref "R27") (pin "1") (pinfunction "1_1") (pintype "passive"))
      (node (ref "R62") (pin "1") (pinfunction "1_1") (pintype "passive"))
      (node (ref "R63") (pin "1") (pinfunction "1_1") (pintype "passive"))
      (node (ref "R64") (pin "1") (pinfunction "1_1") (pintype "passive"))
      (node (ref "R65") (pin "1") (pinfunction "1_1") (pintype "passive"))
      (node (ref "R66") (pin "1") (pinfunction "1_1") (pintype "passive"))
      (node (ref "R67") (pin "1") (pinfunction "1_1") (pintype "passive"))
      (node (ref "SJ1") (pin "P$2") (pinfunction "2_P$2") (pintype "passive"))
      (node (ref "SJ10") (pin "P$2") (pinfunction "2_P$2") (pintype "passive"))
      (node (ref "SJ4") (pin "P$2") (pinfunction "2_P$2") (pintype "passive"))
      (node (ref "SJ7") (pin "P$2") (pinfunction "2_P$2") (pintype "passive"))
      (node (ref "U$1") (pin "5V2") (pinfunction "5V2_5V2") (pintype "power_in"))
      (node (ref "U11") (pin "10") (pinfunction "SCL_10") (pintype "input"))
      (node (ref "U11") (pin "16") (pinfunction "VCC_16") (pintype "power_in"))
      (node (ref "U13") (pin "10") (pinfunction "SCL_10") (pintype "input"))
      (node (ref "U13") (pin "16") (pinfunction "VCC_16") (pintype "power_in"))
      (node (ref "U7") (pin "3") (pinfunction "VCC_3") (pintype "power_in"))
      (node (ref "U7B") (pin "3") (pinfunction "VDD_3") (pintype "power_in"))
      (node (ref "X6") (pin "1") (pinfunction "1_1") (pintype "passive"))
    )
    (net (code "3") (name "+12V") (class "Default")
      (node (ref "C10") (pin "1") (pinfunction "1_1") (pintype "passive"))
      (node (ref "C6") (pin "1") (pinfunction "1_1") (pintype "passive"))
      (node (ref "C7") (pin "1") (pinfunction "1_1") (pintype "passive"))
      (node (ref "J3") (pin "1") (pinfunction "1_1") (pintype "passive"))
      (node (ref "JP2") (pin "7") (pinfunction "7_7") (pintype "passive"))
      (node (ref "JP4") (pin "2") (pinfunction "2_2") (pintype "passive"))
      (node (ref "SJ11") (pin "P$2") (pinfunction "2_P$2") (pintype "passive"))
      (node (ref "SJ14") (pin "P$2") (pinfunction "2_P$2") (pintype "passive"))
      (node (ref "SJ2") (pin "P$2") (pinfunction "2_P$2") (pintype "passive"))
      (node (ref "SJ5") (pin "P$2") (pinfunction "2_P$2") (pintype "passive"))
      (node (ref "SJ8") (pin "P$2") (pinfunction "2_P$2") (pintype "passive"))
      (node (ref "U10") (pin "4") (pinfunction "V+_4") (pintype "power_in"))
      (node (ref "U3") (pin "6") (pinfunction "VDD_6") (pintype "power_in"))
      (node (ref "U4") (pin "6") (pinfunction "VDD_6") (pintype "power_in"))
      (node (ref "U5") (pin "6") (pinfunction "VDD_6") (pintype "power_in"))
      (node (ref "U6") (pin "6") (pinfunction "VDD_6") (pintype "power_in"))
      (node (ref "U8") (pin "1") (pinfunction "VIN_1") (pintype "bidirectional"))
      (node (ref "U8B") (pin "5") (pinfunction "IN_5") (pintype "input"))
      (node (ref "U9") (pin "4") (pinfunction "V+_4") (pintype "power_in"))
    )
    (net (code "4") (name "/AGND") (class "Default")
      (node (ref "U$1") (pin "AGND") (pinfunction "AGND_AGND") (pintype "power_in"))
    )
    (net (code "5") (name "/AVDD") (class "Default")
      (node (ref "U$1") (pin "AVDD") (pinfunction "AVDD_AVDD") (pintype "power_in"))
    )
    (net (code "6") (name "/CANH") (class "Default")
      (node (ref "J1") (pin "1") (pinfunction "1_1") (pintype "passive"))
      (node (ref "J2") (pin "1") (pinfunction "1_1") (pintype "passive"))
      (node (ref "U7") (pin "7") (pinfunction "CANH_7") (pintype "bidirectional"))
      (node (ref "U7B") (pin "7") (pinfunction "CANH_7") (pintype "bidirectional"))
    )
    (net (code "7") (name "/CANL") (class "Default")
      (node (ref "J1") (pin "2") (pinfunction "2_2") (pintype "passive"))
      (node (ref "J2") (pin "2") (pinfunction "2_2") (pintype "passive"))
      (node (ref "U7") (pin "6") (pinfunction "CANL_6") (pintype "bidirectional"))
      (node (ref "U7B") (pin "6") (pinfunction "CANL_6") (pintype "bidirectional"))
    )
    (net (code "8") (name "/GND4") (class "Default")
      (node (ref "U$1") (pin "GND4") (pinfunction "GND4_GND4") (pintype "power_in"))
    )
    (net (code "9") (name "/PWR_POS") (class "Default")
      (node (ref "J1") (pin "8") (pinfunction "8_8") (pintype "passive"))
      (node (ref "J2") (pin "8") (pinfunction "8_8") (pintype "passive"))
      (node (ref "R40") (pin "2") (pinfunction "2_2") (pintype "passive"))
    )
    (net (code "10") (name "/U5V") (class "Default")
      (node (ref "U$1") (pin "U5V") (pinfunction "U5V_U5V") (pintype "power_in"))
    )
    (net (code "11") (name "/VBAT") (class "Default")
      (node (ref "U$1") (pin "VBAT") (pinfunction "VBAT_VBAT") (pintype "power_in"))
    )
    (net (code "12") (name "/VDD") (class "Default")
      (node (ref "U$1") (pin "VDD") (pinfunction "VDD_VDD") (pintype "power_in"))
    )
    (net (code "13") (name "CANRX") (class "Default")
      (node (ref "U$1") (pin "PB8") (pinfunction "PB8_PB8") (pintype "bidirectional"))
      (node (ref "U7") (pin "4") (pinfunction "RXD_4") (pintype "output"))
      (node (ref "U7B") (pin "4") (pinfunction "RXD_4") (pintype "bidirectional"))
    )
    (net (code "14") (name "CANTX") (class "Default")
      (node (ref "U$1") (pin "PB9") (pinfunction "PB9_PB9") (pintype "bidirectional"))
      (node (ref "U7") (pin "1") (pinfunction "TXD_1") (pintype "input"))
      (node (ref "U7B") (pin "1") (pinfunction "TXD_1") (pintype "bidirectional"))
    )
    (net (code "15") (name "E_CS") (class "Default")
      (node (ref "JP2") (pin "4") (pinfunction "4_4") (pintype "passive"))
      (node (ref "R23") (pin "2") (pinfunction "2_2") (pintype "passive"))
      (node (ref "U$1") (pin "PC10") (pinfunction "PC10_PC10") (pintype "bidirectional"))
    )
    (net (code "16") (name "E_LAT") (class "Default")
      (node (ref "JP2") (pin "5") (pinfunction "5_5") (pintype "passive"))
      (node (ref "R22") (pin "2") (pinfunction "2_2") (pintype "passive"))
      (node (ref "U$1") (pin "PC11") (pinfunction "PC11_PC11") (pintype "bidirectional"))
    )
    (net (code "17") (name "GND") (class "Default")
      (node (ref "C1") (pin "2") (pinfunction "2_2") (pintype "passive"))
      (node (ref "C10") (pin "2") (pinfunction "2_2") (pintype "passive"))
      (node (ref "C11") (pin "2") (pinfunction "2_2") (pintype "passive"))
      (node (ref "C2") (pin "-") (pinfunction "-_-") (pintype "passive"))
      (node (ref "C3") (pin "2") (pinfunction "2_2") (pintype "passive"))
      (node (ref "C4") (pin "2") (pinfunction "2_2") (pintype "passive"))
      (node (ref "C5") (pin "2") (pinfunction "2_2") (pintype "passive"))
      (node (ref "C6") (pin "2") (pinfunction "2_2") (pintype "passive"))
      (node (ref "C7") (pin "2") (pinfunction "2_2") (pintype "passive"))
      (node (ref "C8") (pin "2") (pinfunction "2_2") (pintype "passive"))
      (node (ref "C9") (pin "2") (pinfunction "2_2") (pintype "passive"))
      (node (ref "D1") (pin "A") (pinfunction "A_A") (pintype "passive"))
      (node (ref "D3") (pin "A") (pinfunction "A_A") (pintype "passive"))
      (node (ref "J1") (pin "3") (pinfunction "3_3") (pintype "passive"))
      (node (ref "J1") (pin "6") (pinfunction "6_6") (pintype "passive"))
      (node (ref "J1") (pin "7") (pinfunction "7_7") (pintype "passive"))
      (node (ref "J2") (pin "3") (pinfunction "3_3") (pintype "passive"))
      (node (ref "J2") (pin "6") (pinfunction "6_6") (pintype "passive"))
      (node (ref "J2") (pin "7") (pinfunction "7_7") (pintype "passive"))
      (node (ref "J3") (pin "2") (pinfunction "2_2") (pintype "passive"))
      (node (ref "J3") (pin "3") (pinfunction "3_3") (pintype "passive"))
      (node (ref "JP1") (pin "4") (pinfunction "4_4") (pintype "passive"))
      (node (ref "JP2") (pin "8") (pinfunction "8_8") (pintype "passive"))
      (node (ref "JP5") (pin "5") (pinfunction "5_5") (pintype "passive"))
      (node (ref "JP5") (pin "6") (pinfunction "6_6") (pintype "passive"))
      (node (ref "JP6") (pin "5") (pinfunction "5_5") (pintype "passive"))
      (node (ref "JP6") (pin "6") (pinfunction "6_6") (pintype "passive"))
      (node (ref "JP7") (pin "5") (pinfunction "5_5") (pintype "passive"))
      (node (ref "JP7") (pin "6") (pinfunction "6_6") (pintype "passive"))
      (node (ref "JP8") (pin "5") (pinfunction "5_5") (pintype "passive"))
      (node (ref "JP8") (pin "6") (pinfunction "6_6") (pintype "passive"))
      (node (ref "PORTA") (pin "5") (pinfunction "5_5") (pintype "passive"))
      (node (ref "PORTB") (pin "5") (pinfunction "5_5") (pintype "passive"))
      (node (ref "PORTC") (pin "5") (pinfunction "5_5") (pintype "passive"))
      (node (ref "Q1") (pin "2") (pinfunction "S_2") (pintype "passive"))
      (node (ref "Q10") (pin "2") (pinfunction "S_2") (pintype "passive"))
      (node (ref "Q11") (pin "2") (pinfunction "S_2") (pintype "passive"))
      (node (ref "Q12") (pin "2") (pinfunction "S_2") (pintype "passive"))
      (node (ref "Q13") (pin "2") (pinfunction "S_2") (pintype "passive"))
      (node (ref "Q14") (pin "2") (pinfunction "S_2") (pintype "passive"))
      (node (ref "Q15") (pin "2") (pinfunction "S_2") (pintype "passive"))
      (node (ref "Q16") (pin "2") (pinfunction "S_2") (pintype "passive"))
      (node (ref "Q2") (pin "2") (pinfunction "S_2") (pintype "passive"))
      (node (ref "Q3") (pin "2") (pinfunction "S_2") (pintype "passive"))
      (node (ref "Q4") (pin "2") (pinfunction "S_2") (pintype "passive"))
      (node (ref "Q5") (pin "2") (pinfunction "S_2") (pintype "passive"))
      (node (ref "Q6") (pin "2") (pinfunction "S_2") (pintype "passive"))
      (node (ref "Q7") (pin "2") (pinfunction "S_2") (pintype "passive"))
      (node (ref "Q8") (pin "2") (pinfunction "S_2") (pintype "passive"))
      (node (ref "Q9") (pin "2") (pinfunction "S_2") (pintype "passive"))
      (node (ref "R2") (pin "1") (pinfunction "1_1") (pintype "passive"))
      (node (ref "R61") (pin "2") (pinfunction "2_2") (pintype "passive"))
      (node (ref "SJ12") (pin "P$2") (pinfunction "2_P$2") (pintype "passive"))
      (node (ref "SJ3") (pin "2") (pinfunction "2_2") (pintype "passive"))
      (node (ref "SJ6") (pin "P$2") (pinfunction "2_P$2") (pintype "passive"))
      (node (ref "SJ9") (pin "2") (pinfunction "2_2") (pintype "passive"))
      (node (ref "U$1") (pin "GND3") (pinfunction "GND3_GND3") (pintype "power_in"))
      (node (ref "U$1") (pin "GND5") (pinfunction "GND5_GND5") (pintype "power_in"))
      (node (ref "U$1") (pin "GND6") (pinfunction "GND6_GND6") (pintype "power_in"))
      (node (ref "U$1") (pin "GND7") (pinfunction "GND7_GND7") (pintype "power_in"))
      (node (ref "U$1") (pin "GND8") (pinfunction "GND8_GND8") (pintype "power_in"))
      (node (ref "U1") (pin "6") (pinfunction "INH_6") (pintype "input"))
      (node (ref "U1") (pin "8") (pinfunction "GND_8") (pintype "power_in"))
      (node (ref "U10") (pin "11") (pinfunction "V-_11") (pintype "power_in"))
      (node (ref "U11") (pin "13") (pinfunction "G_13") (pintype "input"))
      (node (ref "U11") (pin "8") (pinfunction "GND_8") (pintype "power_in"))
      (node (ref "U13") (pin "13") (pinfunction "G_13") (pintype "input"))
      (node (ref "U13") (pin "8") (pinfunction "GND_8") (pintype "power_in"))
      (node (ref "U2") (pin "6") (pinfunction "INH_6") (pintype "input"))
      (node (ref "U2") (pin "8") (pinfunction "GND_8") (pintype "power_in"))
      (node (ref "U3") (pin "3") (pinfunction "VSS_3") (pintype "power_in"))
      (node (ref "U4") (pin "3") (pinfunction "VSS_3") (pintype "power_in"))
      (node (ref "U5") (pin "3") (pinfunction "VSS_3") (pintype "power_in"))
      (node (ref "U6") (pin "3") (pinfunction "VSS_3") (pintype "power_in"))
      (node (ref "U7") (pin "2") (pinfunction "GND_2") (pintype "power_in"))
      (node (ref "U7B") (pin "2") (pinfunction "VSS_2") (pintype "power_in"))
      (node (ref "U8") (pin "4") (pinfunction "SD_4") (pintype "bidirectional"))
      (node (ref "U8") (pin "5") (pinfunction "GND1_5") (pintype "power_in"))
      (node (ref "U8") (pin "6") (pinfunction "GND2_6") (pintype "power_in"))
      (node (ref "U8") (pin "7") (pinfunction "GND3_7") (pintype "power_in"))
      (node (ref "U8") (pin "8") (pinfunction "GND4_8") (pintype "power_in"))
      (node (ref "U8B") (pin "2") (pinfunction "GNDSIG_2") (pintype "input"))
      (node (ref "U8B") (pin "3") (pinfunction "~{ON/OFF}_3") (pintype "input"))
      (node (ref "U8B") (pin "4") (pinfunction "GND_4") (pintype "power_in"))
      (node (ref "U9") (pin "11") (pinfunction "V-_11") (pintype "power_in"))
      (node (ref "X6") (pin "2") (pinfunction "2_2") (pintype "passive"))
    )
    (net (code "18") (name "I2CSCL") (class "Default")
      (node (ref "JP1") (pin "1") (pinfunction "1_1") (pintype "passive"))
      (node (ref "R62") (pin "2") (pinfunction "2_2") (pintype "passive"))
      (node (ref "U$1") (pin "PB6") (pinfunction "PB6_PB6") (pintype "bidirectional"))
    )
    (net (code "19") (name "I2CSDA") (class "Default")
      (node (ref "JP1") (pin "2") (pinfunction "2_2") (pintype "passive"))
      (node (ref "R63") (pin "2") (pinfunction "2_2") (pintype "passive"))
      (node (ref "U$1") (pin "PB7") (pinfunction "PB7_PB7") (pintype "bidirectional"))
    )
    (net (code "20") (name "ILAT") (class "Default")
      (node (ref "U$1") (pin "PA6") (pinfunction "PA6_PA6") (pintype "bidirectional"))
      (node (ref "U1") (pin "15") (pinfunction "SH/~{LD}_15") (pintype "input"))
      (node (ref "U2") (pin "15") (pinfunction "SH/~{LD}_15") (pintype "input"))
    )
    (net (code "21") (name "MISO") (class "Default")
      (node (ref "JP2") (pin "1") (pinfunction "1_1") (pintype "passive"))
      (node (ref "U$1") (pin "PB4") (pinfunction "PB4_PB4") (pintype "bidirectional"))
    )
    (net (code "22") (name "MISO2") (class "Default")
      (node (ref "SJ13") (pin "P$2") (pinfunction "2_P$2") (pintype "passive"))
      (node (ref "U$1") (pin "PC2") (pinfunction "PC2_PC2") (pintype "bidirectional"))
      (node (ref "U2") (pin "13") (pinfunction "QH_13") (pintype "output"))
    )
    (net (code "23") (name "MOSI") (class "Default")
      (node (ref "R20") (pin "1") (pinfunction "1_1") (pintype "passive"))
      (node (ref "SJ15") (pin "1") (pinfunction "1_1") (pintype "passive"))
      (node (ref "SJ17") (pin "P$2") (pinfunction "2_P$2") (pintype "passive"))
      (node (ref "U$1") (pin "PB5") (pinfunction "PB5_PB5") (pintype "bidirectional"))
      (node (ref "U11") (pin "14") (pinfunction "SER_14") (pintype "input"))
    )
    (net (code "24") (name "Net-(D2-PadA)") (class "Default")
      (node (ref "D2") (pin "A") (pinfunction "A_A") (pintype "passive"))
      (node (ref "D4") (pin "A") (pinfunction "A_A") (pintype "passive"))
      (node (ref "JP4") (pin "4") (pinfunction "4_4") (pintype "passive"))
    )
    (net (code "25") (name "Net-(D2-PadC)") (class "Default")
      (node (ref "D2") (pin "C") (pinfunction "C_C") (pintype "passive"))
      (node (ref "D4") (pin "C") (pinfunction "C_C") (pintype "passive"))
      (node (ref "JP4") (pin "1") (pinfunction "1_1") (pintype "passive"))
    )
    (net (code "26") (name "Net-(J1-Pad4)") (class "Default")
      (node (ref "J1") (pin "4") (pinfunction "4_4") (pintype "passive"))
      (node (ref "J2") (pin "4") (pinfunction "4_4") (pintype "passive"))
    )
    (net (code "27") (name "Net-(J1-Pad5)") (class "Default")
      (node (ref "J1") (pin "5") (pinfunction "5_5") (pintype "passive"))
      (node (ref "J2") (pin "5") (pinfunction "5_5") (pintype "passive"))
    )
    (net (code "28") (name "Net-(JP4-Pad3)") (class "Default")
      (node (ref "JP4") (pin "3") (pinfunction "3_3") (pintype "passive"))
      (node (ref "R40") (pin "1") (pinfunction "1_1") (pintype "passive"))
    )
    (net (code "29") (name "Net-(PORTA-Pad1)") (class "Default")
      (node (ref "PORTA") (pin "1") (pinfunction "1_1") (pintype "passive"))
      (node (ref "R44") (pin "2") (pinfunction "2_2") (pintype "passive"))
      (node (ref "R53") (pin "2") (pinfunction "2_2") (pintype "passive"))
      (node (ref "RN3") (pin "1") (pinfunction "1_1") (pintype "passive"))
      (node (ref "RN4") (pin "9") (pinfunction "9_9") (pintype "passive"))
      (node (ref "X1") (pin "1") (pinfunction "1_1") (pintype "passive"))
    )
    (net (code "30") (name "Net-(PORTB-Pad1)") (class "Default")
      (node (ref "PORTB") (pin "1") (pinfunction "1_1") (pintype "passive"))
      (node (ref "R35") (pin "2") (pinfunction "2_2") (pintype "passive"))
      (node (ref "R45") (pin "2") (pinfunction "2_2") (pintype "passive"))
      (node (ref "RN1") (pin "1") (pinfunction "1_1") (pintype "passive"))
      (node (ref "RN2") (pin "9") (pinfunction "9_9") (pintype "passive"))
      (node (ref "X2") (pin "1") (pinfunction "1_1") (pintype "passive"))
    )
    (net (code "31") (name "Net-(Q1-D)") (class "Default")
      (node (ref "Q1") (pin "3") (pinfunction "D_3") (pintype "passive"))
      (node (ref "U12") (pin "18") (pinfunction "O1_18") (pintype "open_collector"))
      (node (ref "X5") (pin "1") (pinfunction "1_1") (pintype "passive"))
    )
    (net (code "32") (name "Net-(Q1-G)") (class "Default")
      (node (ref "Q1") (pin "1") (pinfunction "G_1") (pintype "passive"))
      (node (ref "R3") (pin "2") (pinfunction "2_2") (pintype "passive"))
    )
    (net (code "33") (name "Net-(Q2-D)") (class "Default")
      (node (ref "Q2") (pin "3") (pinfunction "D_3") (pintype "passive"))
      (node (ref "U12") (pin "17") (pinfunction "O2_17") (pintype "open_collector"))
      (node (ref "X5") (pin "2") (pinfunction "2_2") (pintype "passive"))
    )
    (net (code "34") (name "Net-(Q2-G)") (class "Default")
      (node (ref "Q2") (pin "1") (pinfunction "G_1") (pintype "passive"))
      (node (ref "R4") (pin "2") (pinfunction "2_2") (pintype "passive"))
    )
    (net (code "35") (name "Net-(Q3-D)") (class "Default")
      (node (ref "Q3") (pin "3") (pinfunction "D_3") (pintype "passive"))
      (node (ref "U12") (pin "16") (pinfunction "O3_16") (pintype "open_collector"))
      (node (ref "X5") (pin "3") (pinfunction "3_3") (pintype "passive"))
    )
    (net (code "36") (name "Net-(Q3-G)") (class "Default")
      (node (ref "Q3") (pin "1") (pinfunction "G_1") (pintype "passive"))
      (node (ref "R5") (pin "2") (pinfunction "2_2") (pintype "passive"))
    )
    (net (code "37") (name "Net-(Q4-D)") (class "Default")
      (node (ref "Q4") (pin "3") (pinfunction "D_3") (pintype "passive"))
      (node (ref "U12") (pin "15") (pinfunction "O4_15") (pintype "open_collector"))
      (node (ref "X5") (pin "4") (pinfunction "4_4") (pintype "passive"))
    )
    (net (code "38") (name "Net-(Q4-G)") (class "Default")
      (node (ref "Q4") (pin "1") (pinfunction "G_1") (pintype "passive"))
      (node (ref "R6") (pin "2") (pinfunction "2_2") (pintype "passive"))
    )
    (net (code "39") (name "Net-(Q5-D)") (class "Default")
      (node (ref "Q5") (pin "3") (pinfunction "D_3") (pintype "passive"))
      (node (ref "U12") (pin "14") (pinfunction "O5_14") (pintype "open_collector"))
      (node (ref "X5") (pin "5") (pinfunction "5_5") (pintype "passive"))
    )
    (net (code "40") (name "Net-(Q5-G)") (class "Default")
      (node (ref "Q5") (pin "1") (pinfunction "G_1") (pintype "passive"))
      (node (ref "R7") (pin "2") (pinfunction "2_2") (pintype "passive"))
    )
    (net (code "41") (name "Net-(Q6-D)") (class "Default")
      (node (ref "Q6") (pin "3") (pinfunction "D_3") (pintype "passive"))
      (node (ref "U12") (pin "13") (pinfunction "O6_13") (pintype "open_collector"))
      (node (ref "X5") (pin "6") (pinfunction "6_6") (pintype "passive"))
    )
    (net (code "42") (name "Net-(Q6-G)") (class "Default")
      (node (ref "Q6") (pin "1") (pinfunction "G_1") (pintype "passive"))
      (node (ref "R8") (pin "2") (pinfunction "2_2") (pintype "passive"))
    )
    (net (code "43") (name "Net-(Q7-D)") (class "Default")
      (node (ref "Q7") (pin "3") (pinfunction "D_3") (pintype "passive"))
      (node (ref "U12") (pin "12") (pinfunction "O7_12") (pintype "open_collector"))
      (node (ref "X5") (pin "7") (pinfunction "7_7") (pintype "passive"))
    )
    (net (code "44") (name "Net-(Q7-G)") (class "Default")
      (node (ref "Q7") (pin "1") (pinfunction "G_1") (pintype "passive"))
      (node (ref "R9") (pin "2") (pinfunction "2_2") (pintype "passive"))
    )
    (net (code "45") (name "Net-(Q8-D)") (class "Default")
      (node (ref "Q8") (pin "3") (pinfunction "D_3") (pintype "passive"))
      (node (ref "U12") (pin "11") (pinfunction "O8_11") (pintype "open_collector"))
      (node (ref "X5") (pin "8") (pinfunction "8_8") (pintype "passive"))
    )
    (net (code "46") (name "Net-(Q8-G)") (class "Default")
      (node (ref "Q8") (pin "1") (pinfunction "G_1") (pintype "passive"))
      (node (ref "R10") (pin "2") (pinfunction "2_2") (pintype "passive"))
    )
    (net (code "47") (name "Net-(Q9-D)") (class "Default")
      (node (ref "Q9") (pin "3") (pinfunction "D_3") (pintype "passive"))
      (node (ref "U14") (pin "18") (pinfunction "O1_18") (pintype "open_collector"))
      (node (ref "X4") (pin "1") (pinfunction "1_1") (pintype "passive"))
    )
    (net (code "48") (name "Net-(Q9-G)") (class "Default")
      (node (ref "Q9") (pin "1") (pinfunction "G_1") (pintype "passive"))
      (node (ref "R11") (pin "2") (pinfunction "2_2") (pintype "passive"))
    )
    (net (code "49") (name "Net-(Q10-D)") (class "Default")
      (node (ref "Q10") (pin "3") (pinfunction "D_3") (pintype "passive"))
      (node (ref "U14") (pin "17") (pinfunction "O2_17") (pintype "open_collector"))
      (node (ref "X4") (pin "2") (pinfunction "2_2") (pintype "passive"))
    )
    (net (code "50") (name "Net-(Q10-G)") (class "Default")
      (node (ref "Q10") (pin "1") (pinfunction "G_1") (pintype "passive"))
      (node (ref "R12") (pin "2") (pinfunction "2_2") (pintype "passive"))
    )
    (net (code "51") (name "Net-(Q11-D)") (class "Default")
      (node (ref "Q11") (pin "3") (pinfunction "D_3") (pintype "passive"))
      (node (ref "U14") (pin "16") (pinfunction "O3_16") (pintype "open_collector"))
      (node (ref "X4") (pin "3") (pinfunction "3_3") (pintype "passive"))
    )
    (net (code "52") (name "Net-(Q11-G)") (class "Default")
      (node (ref "Q11") (pin "1") (pinfunction "G_1") (pintype "passive"))
      (node (ref "R13") (pin "2") (pinfunction "2_2") (pintype "passive"))
    )
    (net (code "53") (name "Net-(Q12-D)") (class "Default")
      (node (ref "Q12") (pin "3") (pinfunction "D_3") (pintype "passive"))
      (node (ref "U14") (pin "15") (pinfunction "O4_15") (pintype "open_collector"))
      (node (ref "X4") (pin "4") (pinfunction "4_4") (pintype "passive"))
    )
    (net (code "54") (name "Net-(Q12-G)") (class "Default")
      (node (ref "Q12") (pin "1") (pinfunction "G_1") (pintype "passive"))
      (node (ref "R14") (pin "2") (pinfunction "2_2") (pintype "passive"))
    )
    (net (code "55") (name "Net-(Q13-D)") (class "Default")
      (node (ref "Q13") (pin "3") (pinfunction "D_3") (pintype "passive"))
      (node (ref "U14") (pin "14") (pinfunction "O5_14") (pintype "open_collector"))
      (node (ref "X4") (pin "5") (pinfunction "5_5") (pintype "passive"))
    )
    (net (code "56") (name "Net-(Q13-G)") (class "Default")
      (node (ref "Q13") (pin "1") (pinfunction "G_1") (pintype "passive"))
      (node (ref "R15") (pin "2") (pinfunction "2_2") (pintype "passive"))
    )
    (net (code "57") (name "Net-(Q14-D)") (class "Default")
      (node (ref "Q14") (pin "3") (pinfunction "D_3") (pintype "passive"))
      (node (ref "U14") (pin "13") (pinfunction "O6_13") (pintype "open_collector"))
      (node (ref "X4") (pin "6") (pinfunction "6_6") (pintype "passive"))
    )
    (net (code "58") (name "Net-(Q14-G)") (class "Default")
      (node (ref "Q14") (pin "1") (pinfunction "G_1") (pintype "passive"))
      (node (ref "R16") (pin "2") (pinfunction "2_2") (pintype "passive"))
    )
    (net (code "59") (name "Net-(Q15-D)") (class "Default")
      (node (ref "Q15") (pin "3") (pinfunction "D_3") (pintype "passive"))
      (node (ref "U14") (pin "12") (pinfunction "O7_12") (pintype "open_collector"))
      (node (ref "X4") (pin "7") (pinfunction "7_7") (pintype "passive"))
    )
    (net (code "60") (name "Net-(Q15-G)") (class "Default")
      (node (ref "Q15") (pin "1") (pinfunction "G_1") (pintype "passive"))
      (node (ref "R17") (pin "2") (pinfunction "2_2") (pintype "passive"))
    )
    (net (code "61") (name "Net-(Q16-D)") (class "Default")
      (node (ref "Q16") (pin "3") (pinfunction "D_3") (pintype "passive"))
      (node (ref "U14") (pin "11") (pinfunction "O8_11") (pintype "open_collector"))
      (node (ref "X4") (pin "8") (pinfunction "8_8") (pintype "passive"))
    )
    (net (code "62") (name "Net-(Q16-G)") (class "Default")
      (node (ref "Q16") (pin "1") (pinfunction "G_1") (pintype "passive"))
      (node (ref "R18") (pin "2") (pinfunction "2_2") (pintype "passive"))
    )
    (net (code "63") (name "Net-(RN1A-2)") (class "Default")
      (node (ref "R35") (pin "1") (pinfunction "1_1") (pintype "passive"))
      (node (ref "RN1") (pin "16") (pinfunction "2_16") (pintype "passive"))
      (node (ref "U2") (pin "14") (pinfunction "H_14") (pintype "input"))
    )
    (net (code "64") (name "Net-(RN1B-1)") (class "Default")
      (node (ref "PORTB") (pin "2") (pinfunction "2_2") (pintype "passive"))
      (node (ref "R34") (pin "2") (pinfunction "2_2") (pintype "passive"))
      (node (ref "R46") (pin "2") (pinfunction "2_2") (pintype "passive"))
      (node (ref "RN1") (pin "2") (pinfunction "1_2") (pintype "passive"))
      (node (ref "RN2") (pin "8") (pinfunction "8_8") (pintype "passive"))
      (node (ref "X2") (pin "2") (pinfunction "2_2") (pintype "passive"))
    )
    (net (code "65") (name "Net-(RN1B-2)") (class "Default")
      (node (ref "R34") (pin "1") (pinfunction "1_1") (pintype "passive"))
      (node (ref "RN1") (pin "15") (pinfunction "2_15") (pintype "passive"))
      (node (ref "U2") (pin "12") (pinfunction "G_12") (pintype "input"))
    )
    (net (code "66") (name "Net-(RN1C-1)") (class "Default")
      (node (ref "PORTB") (pin "3") (pinfunction "3_3") (pintype "passive"))
      (node (ref "R33") (pin "2") (pinfunction "2_2") (pintype "passive"))
      (node (ref "R47") (pin "2") (pinfunction "2_2") (pintype "passive"))
      (node (ref "RN1") (pin "3") (pinfunction "1_3") (pintype "passive"))
      (node (ref "RN2") (pin "7") (pinfunction "7_7") (pintype "passive"))
      (node (ref "X2") (pin "3") (pinfunction "3_3") (pintype "passive"))
    )
    (net (code "67") (name "Net-(RN1C-2)") (class "Default")
      (node (ref "R33") (pin "1") (pinfunction "1_1") (pintype "passive"))
      (node (ref "RN1") (pin "14") (pinfunction "2_14") (pintype "passive"))
      (node (ref "U2") (pin "11") (pinfunction "F_11") (pintype "input"))
    )
    (net (code "68") (name "Net-(RN1D-1)") (class "Default")
      (node (ref "PORTB") (pin "4") (pinfunction "4_4") (pintype "passive"))
      (node (ref "R32") (pin "2") (pinfunction "2_2") (pintype "passive"))
      (node (ref "R48") (pin "2") (pinfunction "2_2") (pintype "passive"))
      (node (ref "RN1") (pin "4") (pinfunction "1_4") (pintype "passive"))
      (node (ref "RN2") (pin "6") (pinfunction "6_6") (pintype "passive"))
      (node (ref "X2") (pin "4") (pinfunction "4_4") (pintype "passive"))
    )
    (net (code "69") (name "Net-(RN1D-2)") (class "Default")
      (node (ref "R32") (pin "1") (pinfunction "1_1") (pintype "passive"))
      (node (ref "RN1") (pin "13") (pinfunction "2_13") (pintype "passive"))
      (node (ref "U2") (pin "10") (pinfunction "E_10") (pintype "input"))
    )
    (net (code "70") (name "Net-(RN1E-1)") (class "Default")
      (node (ref "PORTB") (pin "7") (pinfunction "7_7") (pintype "passive"))
      (node (ref "R31") (pin "2") (pinfunction "2_2") (pintype "passive"))
      (node (ref "R49") (pin "2") (pinfunction "2_2") (pintype "passive"))
      (node (ref "RN1") (pin "5") (pinfunction "1_5") (pintype "passive"))
      (node (ref "RN2") (pin "5") (pinfunction "5_5") (pintype "passive"))
      (node (ref "X2") (pin "5") (pinfunction "5_5") (pintype "passive"))
    )
    (net (code "71") (name "Net-(RN1E-2)") (class "Default")
      (node (ref "R31") (pin "1") (pinfunction "1_1") (pintype "passive"))
      (node (ref "RN1") (pin "12") (pinfunction "2_12") (pintype "passive"))
      (node (ref "U2") (pin "5") (pinfunction "D_5") (pintype "input"))
    )
    (net (code "72") (name "Net-(RN1F-1)") (class "Default")
      (node (ref "PORTB") (pin "8") (pinfunction "8_8") (pintype "passive"))
      (node (ref "R30") (pin "2") (pinfunction "2_2") (pintype "passive"))
      (node (ref "R50") (pin "2") (pinfunction "2_2") (pintype "passive"))
      (node (ref "RN1") (pin "6") (pinfunction "1_6") (pintype "passive"))
      (node (ref "RN2") (pin "4") (pinfunction "4_4") (pintype "passive"))
      (node (ref "X2") (pin "6") (pinfunction "6_6") (pintype "passive"))
    )
    (net (code "73") (name "Net-(RN1F-2)") (class "Default")
      (node (ref "R30") (pin "1") (pinfunction "1_1") (pintype "passive"))
      (node (ref "RN1") (pin "11") (pinfunction "2_11") (pintype "passive"))
      (node (ref "U2") (pin "4") (pinfunction "C_4") (pintype "input"))
    )
    (net (code "74") (name "Net-(RN1G-1)") (class "Default")
      (node (ref "PORTB") (pin "9") (pinfunction "9_9") (pintype "passive"))
      (node (ref "R29") (pin "2") (pinfunction "2_2") (pintype "passive"))
      (node (ref "R51") (pin "2") (pinfunction "2_2") (pintype "passive"))
      (node (ref "RN1") (pin "7") (pinfunction "1_7") (pintype "passive"))
      (node (ref "RN2") (pin "3") (pinfunction "3_3") (pintype "passive"))
      (node (ref "X2") (pin "7") (pinfunction "7_7") (pintype "passive"))
    )
    (net (code "75") (name "Net-(RN1G-2)") (class "Default")
      (node (ref "R29") (pin "1") (pinfunction "1_1") (pintype "passive"))
      (node (ref "RN1") (pin "10") (pinfunction "2_10") (pintype "passive"))
      (node (ref "U2") (pin "3") (pinfunction "B_3") (pintype "input"))
    )
    (net (code "76") (name "Net-(RN1H-1)") (class "Default")
      (node (ref "PORTB") (pin "10") (pinfunction "10_10") (pintype "passive"))
      (node (ref "R28") (pin "2") (pinfunction "2_2") (pintype "passive"))
      (node (ref "R52") (pin "2") (pinfunction "2_2") (pintype "passive"))
      (node (ref "RN1") (pin "8") (pinfunction "1_8") (pintype "passive"))
      (node (ref "RN2") (pin "2") (pinfunction "2_2") (pintype "passive"))
      (node (ref "X2") (pin "8") (pinfunction "8_8") (pintype "passive"))
    )
    (net (code "77") (name "Net-(RN1H-2)") (class "Default")
      (node (ref "R28") (pin "1") (pinfunction "1_1") (pintype "passive"))
      (node (ref "RN1") (pin "9") (pinfunction "2_9") (pintype "passive"))
      (node (ref "U2") (pin "2") (pinfunction "A_2") (pintype "input"))
    )
    (net (code "78") (name "Net-(RN3A-2)") (class "Default")
      (node (ref "R44") (pin "1") (pinfunction "1_1") (pintype "passive"))
      (node (ref "RN3") (pin "16") (pinfunction "2_16") (pintype "passive"))
      (node (ref "U1") (pin "14") (pinfunction "H_14") (pintype "input"))
    )
    (net (code "79") (name "Net-(RN3B-1)") (class "Default")
      (node (ref "PORTA") (pin "2") (pinfunction "2_2") (pintype "passive"))
      (node (ref "R43") (pin "2") (pinfunction "2_2") (pintype "passive"))
      (node (ref "R54") (pin "2") (pinfunction "2_2") (pintype "passive"))
      (node (ref "RN3") (pin "2") (pinfunction "1_2") (pintype "passive"))
      (node (ref "RN4") (pin "8") (pinfunction "8_8") (pintype "passive"))
      (node (ref "X1") (pin "2") (pinfunction "2_2") (pintype "passive"))
    )
    (net (code "80") (name "Net-(RN3B-2)") (class "Default")
      (node (ref "R43") (pin "1") (pinfunction "1_1") (pintype "passive"))
      (node (ref "RN3") (pin "15") (pinfunction "2_15") (pintype "passive"))
      (node (ref "U1") (pin "12") (pinfunction "G_12") (pintype "input"))
    )
    (net (code "81") (name "Net-(RN3C-1)") (class "Default")
      (node (ref "PORTA") (pin "3") (pinfunction "3_3") (pintype "passive"))
      (node (ref "R42") (pin "2") (pinfunction "2_2") (pintype "passive"))
      (node (ref "R55") (pin "2") (pinfunction "2_2") (pintype "passive"))
      (node (ref "RN3") (pin "3") (pinfunction "1_3") (pintype "passive"))
      (node (ref "RN4") (pin "7") (pinfunction "7_7") (pintype "passive"))
      (node (ref "X1") (pin "3") (pinfunction "3_3") (pintype "passive"))
    )
    (net (code "82") (name "Net-(RN3C-2)") (class "Default")
      (node (ref "R42") (pin "1") (pinfunction "1_1") (pintype "passive"))
      (node (ref "RN3") (pin "14") (pinfunction "2_14") (pintype "passive"))
      (node (ref "U1") (pin "11") (pinfunction "F_11") (pintype "input"))
    )
    (net (code "83") (name "Net-(RN3D-1)") (class "Default")
      (node (ref "PORTA") (pin "4") (pinfunction "4_4") (pintype "passive"))
      (node (ref "R41") (pin "2") (pinfunction "2_2") (pintype "passive"))
      (node (ref "R56") (pin "2") (pinfunction "2_2") (pintype "passive"))
      (node (ref "RN3") (pin "4") (pinfunction "1_4") (pintype "passive"))
      (node (ref "RN4") (pin "6") (pinfunction "6_6") (pintype "passive"))
      (node (ref "X1") (pin "4") (pinfunction "4_4") (pintype "passive"))
    )
    (net (code "84") (name "Net-(RN3D-2)") (class "Default")
      (node (ref "R41") (pin "1") (pinfunction "1_1") (pintype "passive"))
      (node (ref "RN3") (pin "13") (pinfunction "2_13") (pintype "passive"))
      (node (ref "U1") (pin "10") (pinfunction "E_10") (pintype "input"))
    )
    (net (code "85") (name "Net-(RN3E-1)") (class "Default")
      (node (ref "PORTA") (pin "7") (pinfunction "7_7") (pintype "passive"))
      (node (ref "R39") (pin "2") (pinfunction "2_2") (pintype "passive"))
      (node (ref "R57") (pin "2") (pinfunction "2_2") (pintype "passive"))
      (node (ref "RN3") (pin "5") (pinfunction "1_5") (pintype "passive"))
      (node (ref "RN4") (pin "5") (pinfunction "5_5") (pintype "passive"))
      (node (ref "X1") (pin "5") (pinfunction "5_5") (pintype "passive"))
    )
    (net (code "86") (name "Net-(RN3E-2)") (class "Default")
      (node (ref "R39") (pin "1") (pinfunction "1_1") (pintype "passive"))
      (node (ref "RN3") (pin "12") (pinfunction "2_12") (pintype "passive"))
      (node (ref "U1") (pin "5") (pinfunction "D_5") (pintype "input"))
    )
    (net (code "87") (name "Net-(RN3F-1)") (class "Default")
      (node (ref "PORTA") (pin "8") (pinfunction "8_8") (pintype "passive"))
      (node (ref "R38") (pin "2") (pinfunction "2_2") (pintype "passive"))
      (node (ref "R58") (pin "2") (pinfunction "2_2") (pintype "passive"))
      (node (ref "RN3") (pin "6") (pinfunction "1_6") (pintype "passive"))
      (node (ref "RN4") (pin "4") (pinfunction "4_4") (pintype "passive"))
      (node (ref "X1") (pin "6") (pinfunction "6_6") (pintype "passive"))
    )
    (net (code "88") (name "Net-(RN3F-2)") (class "Default")
      (node (ref "R38") (pin "1") (pinfunction "1_1") (pintype "passive"))
      (node (ref "RN3") (pin "11") (pinfunction "2_11") (pintype "passive"))
      (node (ref "U1") (pin "4") (pinfunction "C_4") (pintype "input"))
    )
    (net (code "89") (name "Net-(RN3G-1)") (class "Default")
      (node (ref "PORTA") (pin "9") (pinfunction "9_9") (pintype "passive"))
      (node (ref "R37") (pin "2") (pinfunction "2_2") (pintype "passive"))
      (node (ref "R59") (pin "2") (pinfunction "2_2") (pintype "passive"))
      (node (ref "RN3") (pin "7") (pinfunction "1_7") (pintype "passive"))
      (node (ref "RN4") (pin "3") (pinfunction "3_3") (pintype "passive"))
      (node (ref "X1") (pin "7") (pinfunction "7_7") (pintype "passive"))
    )
    (net (code "90") (name "Net-(RN3G-2)") (class "Default")
      (node (ref "R37") (pin "1") (pinfunction "1_1") (pintype "passive"))
      (node (ref "RN3") (pin "10") (pinfunction "2_10") (pintype "passive"))
      (node (ref "U1") (pin "3") (pinfunction "B_3") (pintype "input"))
    )
    (net (code "91") (name "Net-(RN3H-1)") (class "Default")
      (node (ref "PORTA") (pin "10") (pinfunction "10_10") (pintype "passive"))
      (node (ref "R36") (pin "2") (pinfunction "2_2") (pintype "passive"))
      (node (ref "R60") (pin "2") (pinfunction "2_2") (pintype "passive"))
      (node (ref "RN3") (pin "8") (pinfunction "1_8") (pintype "passive"))
      (node (ref "RN4") (pin "2") (pinfunction "2_2") (pintype "passive"))
      (node (ref "X1") (pin "8") (pinfunction "8_8") (pintype "passive"))
    )
    (net (code "92") (name "Net-(RN3H-2)") (class "Default")
      (node (ref "R36") (pin "1") (pinfunction "1_1") (pintype "passive"))
      (node (ref "RN3") (pin "9") (pinfunction "2_9") (pintype "passive"))
      (node (ref "U1") (pin "2") (pinfunction "A_2") (pintype "input"))
    )
    (net (code "93") (name "Net-(SJ1-1)") (class "Default")
      (node (ref "SJ1") (pin "P$1") (pinfunction "1_P$1") (pintype "passive"))
      (node (ref "SJ2") (pin "P$1") (pinfunction "1_P$1") (pintype "passive"))
      (node (ref "SJ3") (pin "1") (pinfunction "1_1") (pintype "passive"))
      (node (ref "U12") (pin "9") (pinfunction "GND_9") (pintype "power_in"))
    )
    (net (code "94") (name "Net-(SJ4-1)") (class "Default")
      (node (ref "SJ4") (pin "P$1") (pinfunction "1_P$1") (pintype "passive"))
      (node (ref "SJ5") (pin "P$1") (pinfunction "1_P$1") (pintype "passive"))
      (node (ref "SJ6") (pin "P$1") (pinfunction "1_P$1") (pintype "passive"))
      (node (ref "U12") (pin "10") (pinfunction "CD+_10") (pintype "passive"))
    )
    (net (code "95") (name "Net-(SJ7-1)") (class "Default")
      (node (ref "SJ7") (pin "P$1") (pinfunction "1_P$1") (pintype "passive"))
      (node (ref "SJ8") (pin "P$1") (pinfunction "1_P$1") (pintype "passive"))
      (node (ref "SJ9") (pin "1") (pinfunction "1_1") (pintype "passive"))
      (node (ref "U14") (pin "9") (pinfunction "GND_9") (pintype "power_in"))
    )
    (net (code "96") (name "Net-(SJ10-1)") (class "Default")
      (node (ref "SJ10") (pin "P$1") (pinfunction "1_P$1") (pintype "passive"))
      (node (ref "SJ11") (pin "P$1") (pinfunction "1_P$1") (pintype "passive"))
      (node (ref "SJ12") (pin "P$1") (pinfunction "1_P$1") (pintype "passive"))
      (node (ref "U14") (pin "10") (pinfunction "CD+_10") (pintype "passive"))
    )
    (net (code "97") (name "Net-(SJ13-1)") (class "Default")
      (node (ref "SJ13") (pin "P$1") (pinfunction "1_P$1") (pintype "passive"))
      (node (ref "U$1") (pin "PB14") (pinfunction "PB14_PB14") (pintype "bidirectional"))
    )
    (net (code "98") (name "Net-(SJ14-1)") (class "Default")
      (node (ref "SJ14") (pin "P$1") (pinfunction "1_P$1") (pintype "passive"))
      (node (ref "U$1") (pin "VIN2") (pinfunction "VIN2_VIN2") (pintype "power_in"))
    )
    (net (code "99") (name "Net-(SJ16-2)") (class "Default")
      (node (ref "JP2") (pin "2") (pinfunction "2_2") (pintype "passive"))
      (node (ref "SJ15") (pin "2") (pinfunction "2_2") (pintype "passive"))
      (node (ref "SJ16") (pin "P$2") (pinfunction "2_P$2") (pintype "passive"))
    )
    (net (code "100") (name "Net-(SJ18-2)") (class "Default")
      (node (ref "SJ18") (pin "P$2") (pinfunction "2_P$2") (pintype "passive"))
      (node (ref "U7") (pin "5") (pinfunction "VREF_5") (pintype "output"))
      (node (ref "U7B") (pin "5") (pinfunction "VREF_5") (pintype "bidirectional"))
    )
    (net (code "101") (name "Net-(U3A-O)") (class "Default")
      (node (ref "PORTC") (pin "1") (pinfunction "1_1") (pintype "passive"))
      (node (ref "U3") (pin "7") (pinfunction "O_7") (pintype "output"))
      (node (ref "U9") (pin "7") (pinfunction "OUT_7") (pintype "output"))
      (node (ref "X3") (pin "1") (pinfunction "1_1") (pintype "passive"))
    )
    (net (code "102") (name "Net-(U3B-O)") (class "Default")
      (node (ref "PORTC") (pin "2") (pinfunction "2_2") (pintype "passive"))
      (node (ref "U3") (pin "5") (pinfunction "O_5") (pintype "output"))
      (node (ref "U9") (pin "8") (pinfunction "OUT_8") (pintype "output"))
      (node (ref "X3") (pin "2") (pinfunction "2_2") (pintype "passive"))
    )
    (net (code "103") (name "Net-(U4A-O)") (class "Default")
      (node (ref "PORTC") (pin "4") (pinfunction "4_4") (pintype "passive"))
      (node (ref "U4") (pin "7") (pinfunction "O_7") (pintype "output"))
      (node (ref "U9") (pin "14") (pinfunction "OUT_14") (pintype "output"))
      (node (ref "X3") (pin "4") (pinfunction "4_4") (pintype "passive"))
    )
    (net (code "104") (name "Net-(U4B-O)") (class "Default")
      (node (ref "PORTC") (pin "3") (pinfunction "3_3") (pintype "passive"))
      (node (ref "U4") (pin "5") (pinfunction "O_5") (pintype "output"))
      (node (ref "U9") (pin "1") (pinfunction "OUT_1") (pintype "output"))
      (node (ref "X3") (pin "3") (pinfunction "3_3") (pintype "passive"))
    )
    (net (code "105") (name "Net-(U7-RS)") (class "Default")
      (node (ref "R61") (pin "1") (pinfunction "1_1") (pintype "passive"))
      (node (ref "U7") (pin "8") (pinfunction "RS_8") (pintype "input"))
      (node (ref "U7B") (pin "8") (pinfunction "RS_8") (pintype "bidirectional"))
    )
    (net (code "106") (name "Net-(U8-VOUT)") (class "Default")
      (node (ref "D1") (pin "C") (pinfunction "C_C") (pintype "passive"))
      (node (ref "D3") (pin "C") (pinfunction "C_C") (pintype "passive"))
      (node (ref "L1") (pin "2") (pinfunction "2_2") (pintype "passive"))
      (node (ref "U8") (pin "2") (pinfunction "VOUT_2") (pintype "bidirectional"))
      (node (ref "U8B") (pin "7") (pinfunction "OUT_7") (pintype "passive"))
    )
    (net (code "107") (name "Net-(U10A--IN)") (class "Default")
      (node (ref "R1") (pin "1") (pinfunction "1_1") (pintype "passive"))
      (node (ref "R2") (pin "2") (pinfunction "2_2") (pintype "passive"))
      (node (ref "U10") (pin "13") (pinfunction "-IN_13") (pintype "input"))
      (node (ref "U10") (pin "2") (pinfunction "-IN_2") (pintype "input"))
      (node (ref "U10") (pin "6") (pinfunction "-IN_6") (pintype "input"))
      (node (ref "U10") (pin "9") (pinfunction "-IN_9") (pintype "input"))
      (node (ref "U9") (pin "13") (pinfunction "-IN_13") (pintype "input"))
      (node (ref "U9") (pin "2") (pinfunction "-IN_2") (pintype "input"))
      (node (ref "U9") (pin "6") (pinfunction "-IN_6") (pintype "input"))
      (node (ref "U9") (pin "9") (pinfunction "-IN_9") (pintype "input"))
    )
    (net (code "108") (name "Net-(U10A-OUT)") (class "Default")
      (node (ref "PORTC") (pin "9") (pinfunction "9_9") (pintype "passive"))
      (node (ref "U10") (pin "1") (pinfunction "OUT_1") (pintype "output"))
      (node (ref "U6") (pin "5") (pinfunction "O_5") (pintype "output"))
      (node (ref "X3") (pin "7") (pinfunction "7_7") (pintype "passive"))
    )
    (net (code "109") (name "Net-(U10B-OUT)") (class "Default")
      (node (ref "PORTC") (pin "7") (pinfunction "7_7") (pintype "passive"))
      (node (ref "U10") (pin "7") (pinfunction "OUT_7") (pintype "output"))
      (node (ref "U5") (pin "7") (pinfunction "O_7") (pintype "output"))
      (node (ref "X3") (pin "5") (pinfunction "5_5") (pintype "passive"))
    )
    (net (code "110") (name "Net-(U10C-OUT)") (class "Default")
      (node (ref "PORTC") (pin "8") (pinfunction "8_8") (pintype "passive"))
      (node (ref "U10") (pin "8") (pinfunction "OUT_8") (pintype "output"))
      (node (ref "U5") (pin "5") (pinfunction "O_5") (pintype "output"))
      (node (ref "X3") (pin "6") (pinfunction "6_6") (pintype "passive"))
    )
    (net (code "111") (name "Net-(U10D-OUT)") (class "Default")
      (node (ref "PORTC") (pin "10") (pinfunction "10_10") (pintype "passive"))
      (node (ref "U10") (pin "14") (pinfunction "OUT_14") (pintype "output"))
      (node (ref "U6") (pin "7") (pinfunction "O_7") (pintype "output"))
      (node (ref "X3") (pin "8") (pinfunction "8_8") (pintype "passive"))
    )
    (net (code "112") (name "Net-(U11A-QA)") (class "Default")
      (node (ref "R3") (pin "1") (pinfunction "1_1") (pintype "passive"))
      (node (ref "U11") (pin "15") (pinfunction "QA_15") (pintype "tri_state"))
      (node (ref "U12") (pin "1") (pinfunction "I1_1") (pintype "input"))
    )
    (net (code "113") (name "Net-(U11A-QB)") (class "Default")
      (node (ref "R4") (pin "1") (pinfunction "1_1") (pintype "passive"))
      (node (ref "U11") (pin "1") (pinfunction "QB_1") (pintype "tri_state"))
      (node (ref "U12") (pin "2") (pinfunction "I2_2") (pintype "input"))
    )
    (net (code "114") (name "Net-(U11A-QC)") (class "Default")
      (node (ref "R5") (pin "1") (pinfunction "1_1") (pintype "passive"))
      (node (ref "U11") (pin "2") (pinfunction "QC_2") (pintype "tri_state"))
      (node (ref "U12") (pin "3") (pinfunction "I3_3") (pintype "input"))
    )
    (net (code "115") (name "Net-(U11A-QD)") (class "Default")
      (node (ref "R6") (pin "1") (pinfunction "1_1") (pintype "passive"))
      (node (ref "U11") (pin "3") (pinfunction "QD_3") (pintype "tri_state"))
      (node (ref "U12") (pin "4") (pinfunction "I4_4") (pintype "input"))
    )
    (net (code "116") (name "Net-(U11A-QE)") (class "Default")
      (node (ref "R7") (pin "1") (pinfunction "1_1") (pintype "passive"))
      (node (ref "U11") (pin "4") (pinfunction "QE_4") (pintype "tri_state"))
      (node (ref "U12") (pin "5") (pinfunction "I5_5") (pintype "input"))
    )
    (net (code "117") (name "Net-(U11A-QF)") (class "Default")
      (node (ref "R8") (pin "1") (pinfunction "1_1") (pintype "passive"))
      (node (ref "U11") (pin "5") (pinfunction "QF_5") (pintype "tri_state"))
      (node (ref "U12") (pin "6") (pinfunction "I6_6") (pintype "input"))
    )
    (net (code "118") (name "Net-(U11A-QG)") (class "Default")
      (node (ref "R9") (pin "1") (pinfunction "1_1") (pintype "passive"))
      (node (ref "U11") (pin "6") (pinfunction "QG_6") (pintype "tri_state"))
      (node (ref "U12") (pin "7") (pinfunction "I7_7") (pintype "input"))
    )
    (net (code "119") (name "Net-(U11A-QH)") (class "Default")
      (node (ref "R10") (pin "1") (pinfunction "1_1") (pintype "passive"))
      (node (ref "U11") (pin "7") (pinfunction "QH_7") (pintype "tri_state"))
      (node (ref "U12") (pin "8") (pinfunction "I8_8") (pintype "input"))
    )
    (net (code "120") (name "Net-(U13A-QA)") (class "Default")
      (node (ref "R11") (pin "1") (pinfunction "1_1") (pintype "passive"))
      (node (ref "U13") (pin "15") (pinfunction "QA_15") (pintype "tri_state"))
      (node (ref "U14") (pin "1") (pinfunction "I1_1") (pintype "input"))
    )
    (net (code "121") (name "Net-(U13A-QB)") (class "Default")
      (node (ref "R12") (pin "1") (pinfunction "1_1") (pintype "passive"))
      (node (ref "U13") (pin "1") (pinfunction "QB_1") (pintype "tri_state"))
      (node (ref "U14") (pin "2") (pinfunction "I2_2") (pintype "input"))
    )
    (net (code "122") (name "Net-(U13A-QC)") (class "Default")
      (node (ref "R13") (pin "1") (pinfunction "1_1") (pintype "passive"))
      (node (ref "U13") (pin "2") (pinfunction "QC_2") (pintype "tri_state"))
      (node (ref "U14") (pin "3") (pinfunction "I3_3") (pintype "input"))
    )
    (net (code "123") (name "Net-(U13A-QD)") (class "Default")
      (node (ref "R14") (pin "1") (pinfunction "1_1") (pintype "passive"))
      (node (ref "U13") (pin "3") (pinfunction "QD_3") (pintype "tri_state"))
      (node (ref "U14") (pin "4") (pinfunction "I4_4") (pintype "input"))
    )
    (net (code "124") (name "Net-(U13A-QE)") (class "Default")
      (node (ref "R15") (pin "1") (pinfunction "1_1") (pintype "passive"))
      (node (ref "U13") (pin "4") (pinfunction "QE_4") (pintype "tri_state"))
      (node (ref "U14") (pin "5") (pinfunction "I5_5") (pintype "input"))
    )
    (net (code "125") (name "Net-(U13A-QF)") (class "Default")
      (node (ref "R16") (pin "1") (pinfunction "1_1") (pintype "passive"))
      (node (ref "U13") (pin "5") (pinfunction "QF_5") (pintype "tri_state"))
      (node (ref "U14") (pin "6") (pinfunction "I6_6") (pintype "input"))
    )
    (net (code "126") (name "Net-(U13A-QG)") (class "Default")
      (node (ref "R17") (pin "1") (pinfunction "1_1") (pintype "passive"))
      (node (ref "U13") (pin "6") (pinfunction "QG_6") (pintype "tri_state"))
      (node (ref "U14") (pin "7") (pinfunction "I7_7") (pintype "input"))
    )
    (net (code "127") (name "Net-(U13A-QH)") (class "Default")
      (node (ref "R18") (pin "1") (pinfunction "1_1") (pintype "passive"))
      (node (ref "U13") (pin "7") (pinfunction "QH_7") (pintype "tri_state"))
      (node (ref "U14") (pin "8") (pinfunction "I8_8") (pintype "input"))
    )
    (net (code "128") (name "OLAT") (class "Default")
      (node (ref "R21") (pin "1") (pinfunction "1_1") (pintype "passive"))
      (node (ref "U$1") (pin "PA8") (pinfunction "PA8_PA8") (pintype "bidirectional"))
      (node (ref "U11") (pin "12") (pinfunction "RCK_12") (pintype "input"))
      (node (ref "U13") (pin "12") (pinfunction "RCK_12") (pintype "input"))
    )
    (net (code "129") (name "SCK") (class "Default")
      (node (ref "JP2") (pin "3") (pinfunction "3_3") (pintype "passive"))
      (node (ref "R19") (pin "1") (pinfunction "1_1") (pintype "passive"))
      (node (ref "U$1") (pin "PB3") (pinfunction "PB3_PB3") (pintype "bidirectional"))
      (node (ref "U11") (pin "11") (pinfunction "SCK_11") (pintype "input"))
      (node (ref "U13") (pin "11") (pinfunction "SCK_11") (pintype "input"))
    )
    (net (code "130") (name "SCK2") (class "Default")
      (node (ref "U$1") (pin "PB10") (pinfunction "PB10_PB10") (pintype "bidirectional"))
      (node (ref "U1") (pin "7") (pinfunction "CLK_7") (pintype "input"))
      (node (ref "U2") (pin "7") (pinfunction "CLK_7") (pintype "input"))
    )
    (net (code "131") (name "SLNK1") (class "Default")
      (node (ref "SJ17") (pin "P$1") (pinfunction "1_P$1") (pintype "passive"))
      (node (ref "U11") (pin "9") (pinfunction "QH*_9") (pintype "tri_state"))
      (node (ref "U13") (pin "14") (pinfunction "SER_14") (pintype "input"))
    )
    (net (code "132") (name "SLNK2") (class "Default")
      (node (ref "SJ16") (pin "P$1") (pinfunction "1_P$1") (pintype "passive"))
      (node (ref "U13") (pin "9") (pinfunction "QH*_9") (pintype "tri_state"))
    )
    (net (code "133") (name "SLNK3") (class "Default")
      (node (ref "U1") (pin "13") (pinfunction "QH_13") (pintype "output"))
      (node (ref "U2") (pin "1") (pinfunction "SER_1") (pintype "input"))
    )
    (net (code "134") (name "SRV1") (class "Default")
      (node (ref "JP5") (pin "2") (pinfunction "2_2") (pintype "passive"))
      (node (ref "R24") (pin "2") (pinfunction "2_2") (pintype "passive"))
      (node (ref "U$1") (pin "PC9") (pinfunction "PC9_PC9") (pintype "bidirectional"))
    )
    (net (code "135") (name "SRV2") (class "Default")
      (node (ref "JP5") (pin "1") (pinfunction "1_1") (pintype "passive"))
      (node (ref "R25") (pin "2") (pinfunction "2_2") (pintype "passive"))
      (node (ref "U$1") (pin "PC7") (pinfunction "PC7_PC7") (pintype "bidirectional"))
    )
    (net (code "136") (name "SRV3") (class "Default")
      (node (ref "JP6") (pin "2") (pinfunction "2_2") (pintype "passive"))
      (node (ref "R26") (pin "2") (pinfunction "2_2") (pintype "passive"))
      (node (ref "U$1") (pin "PC8") (pinfunction "PC8_PC8") (pintype "bidirectional"))
    )
    (net (code "137") (name "SRV4") (class "Default")
      (node (ref "JP6") (pin "1") (pinfunction "1_1") (pintype "passive"))
      (node (ref "R27") (pin "2") (pinfunction "2_2") (pintype "passive"))
      (node (ref "U$1") (pin "PC6") (pinfunction "PC6_PC6") (pintype "bidirectional"))
    )
    (net (code "138") (name "SRV5") (class "Default")
      (node (ref "JP7") (pin "2") (pinfunction "2_2") (pintype "passive"))
      (node (ref "R64") (pin "2") (pinfunction "2_2") (pintype "passive"))
      (node (ref "U$1") (pin "PF1-PH1") (pinfunction "PF1-PH1_PF1-PH1") (pintype "bidirectional"))
    )
    (net (code "139") (name "SRV6") (class "Default")
      (node (ref "JP7") (pin "1") (pinfunction "1_1") (pintype "passive"))
      (node (ref "R65") (pin "2") (pinfunction "2_2") (pintype "passive"))
      (node (ref "U$1") (pin "PA15") (pinfunction "PA15_PA15") (pintype "bidirectional"))
    )
    (net (code "140") (name "SRV7") (class "Default")
      (node (ref "JP8") (pin "2") (pinfunction "2_2") (pintype "passive"))
      (node (ref "R66") (pin "2") (pinfunction "2_2") (pintype "passive"))
      (node (ref "U$1") (pin "PC12") (pinfunction "PC12_PC12") (pintype "bidirectional"))
    )
    (net (code "141") (name "SRV8") (class "Default")
      (node (ref "JP8") (pin "1") (pinfunction "1_1") (pintype "passive"))
      (node (ref "R67") (pin "2") (pinfunction "2_2") (pintype "passive"))
      (node (ref "U$1") (pin "PD2") (pinfunction "PD2_PD2") (pintype "bidirectional"))
    )
    (net (code "142") (name "TDRV1") (class "Default")
      (node (ref "U$1") (pin "PB12") (pinfunction "PB12_PB12") (pintype "bidirectional"))
      (node (ref "U10") (pin "12") (pinfunction "+IN_12") (pintype "input"))
      (node (ref "U6") (pin "2") (pinfunction "I_2") (pintype "input"))
    )
    (net (code "143") (name "TDRV2") (class "Default")
      (node (ref "U$1") (pin "PB2") (pinfunction "PB2_PB2") (pintype "bidirectional"))
      (node (ref "U10") (pin "3") (pinfunction "+IN_3") (pintype "input"))
      (node (ref "U6") (pin "4") (pinfunction "I_4") (pintype "input"))
    )
    (net (code "144") (name "TDRV3") (class "Default")
      (node (ref "U$1") (pin "PB15") (pinfunction "PB15_PB15") (pintype "bidirectional"))
      (node (ref "U10") (pin "10") (pinfunction "+IN_10") (pintype "input"))
      (node (ref "U5") (pin "4") (pinfunction "I_4") (pintype "input"))
    )
    (net (code "145") (name "TDRV4") (class "Default")
      (node (ref "U$1") (pin "PB1") (pinfunction "PB1_PB1") (pintype "bidirectional"))
      (node (ref "U10") (pin "5") (pinfunction "+IN_5") (pintype "input"))
      (node (ref "U5") (pin "2") (pinfunction "I_2") (pintype "input"))
    )
    (net (code "146") (name "TDRV5") (class "Default")
      (node (ref "U$1") (pin "PA0") (pinfunction "PA0_PA0") (pintype "bidirectional"))
      (node (ref "U4") (pin "2") (pinfunction "I_2") (pintype "input"))
      (node (ref "U9") (pin "12") (pinfunction "+IN_12") (pintype "input"))
    )
    (net (code "147") (name "TDRV6") (class "Default")
      (node (ref "U$1") (pin "PA4") (pinfunction "PA4_PA4") (pintype "bidirectional"))
      (node (ref "U4") (pin "4") (pinfunction "I_4") (pintype "input"))
      (node (ref "U9") (pin "3") (pinfunction "+IN_3") (pintype "input"))
    )
    (net (code "148") (name "TDRV7") (class "Default")
      (node (ref "U$1") (pin "PC3") (pinfunction "PC3_PC3") (pintype "bidirectional"))
      (node (ref "U3") (pin "4") (pinfunction "I_4") (pintype "input"))
      (node (ref "U9") (pin "10") (pinfunction "+IN_10") (pintype "input"))
    )
    (net (code "149") (name "TDRV8") (class "Default")
      (node (ref "U$1") (pin "PC0") (pinfunction "PC0_PC0") (pintype "bidirectional"))
      (node (ref "U3") (pin "2") (pinfunction "I_2") (pintype "input"))
      (node (ref "U9") (pin "5") (pinfunction "+IN_5") (pintype "input"))
    )
    (net (code "150") (name "V+") (class "Default")
      (node (ref "C1") (pin "1") (pinfunction "1_1") (pintype "passive"))
      (node (ref "C2") (pin "+") (pinfunction "+_+") (pintype "passive"))
      (node (ref "L1") (pin "1") (pinfunction "1_1") (pintype "passive"))
      (node (ref "U$1") (pin "E5V") (pinfunction "E5V_E5V") (pintype "power_in"))
      (node (ref "U8") (pin "3") (pinfunction "FB_3") (pintype "bidirectional"))
      (node (ref "U8B") (pin "1") (pinfunction "FB_1") (pintype "input"))
    )
    (net (code "151") (name "unconnected-(H1-MOUNT-PadB3,3)") (class "Default")
      (node (ref "H1") (pin "B3,3") (pinfunction "MOUNT_B3,3") (pintype "passive"))
    )
    (net (code "152") (name "unconnected-(H2-MOUNT-PadB3,3)") (class "Default")
      (node (ref "H2") (pin "B3,3") (pinfunction "MOUNT_B3,3") (pintype "passive"))
    )
    (net (code "153") (name "unconnected-(H3-MOUNT-PadB3,3)") (class "Default")
      (node (ref "H3") (pin "B3,3") (pinfunction "MOUNT_B3,3") (pintype "passive"))
    )
    (net (code "154") (name "unconnected-(H4-MOUNT-PadB3,3)") (class "Default")
      (node (ref "H4") (pin "B3,3") (pinfunction "MOUNT_B3,3") (pintype "passive"))
    )
    (net (code "155") (name "unconnected-(U$1-PadBOOT0)") (class "Default")
      (node (ref "U$1") (pin "BOOT0") (pinfunction "BOOT0_BOOT0") (pintype "bidirectional"))
    )
    (net (code "156") (name "unconnected-(U$1-PadIOREF2)") (class "Default")
      (node (ref "U$1") (pin "IOREF2") (pinfunction "IOREF2_IOREF2") (pintype "input"))
    )
    (net (code "157") (name "unconnected-(U$1-PadNC1-PF7)") (class "Default")
      (node (ref "U$1") (pin "NC1-PF7") (pinfunction "NC1-PF7_NC1-PF7") (pintype "bidirectional"))
    )
    (net (code "158") (name "unconnected-(U$1-PadNC2-PF6)") (class "Default")
      (node (ref "U$1") (pin "NC2-PF6") (pinfunction "NC2-PF6_NC2-PF6") (pintype "bidirectional"))
    )
    (net (code "159") (name "unconnected-(U$1-PadNC3)") (class "Default")
      (node (ref "U$1") (pin "NC3") (pinfunction "NC3_NC3") (pintype "no_connect"))
    )
    (net (code "160") (name "unconnected-(U$1-PadNC4)") (class "Default")
      (node (ref "U$1") (pin "NC4") (pinfunction "NC4_NC4") (pintype "no_connect"))
    )
    (net (code "161") (name "unconnected-(U$1-PadNC5-PD8)") (class "Default")
      (node (ref "U$1") (pin "NC5-PD8") (pinfunction "NC5-PD8_NC5-PD8") (pintype "bidirectional"))
    )
    (net (code "162") (name "unconnected-(U$1-PadNC6-PB11)") (class "Default")
      (node (ref "U$1") (pin "NC6-PB11") (pinfunction "NC6-PB11_NC6-PB11") (pintype "no_connect"))
    )
    (net (code "163") (name "unconnected-(U$1-PadNC7-PF5)") (class "Default")
      (node (ref "U$1") (pin "NC7-PF5") (pinfunction "NC7-PF5_NC7-PF5") (pintype "bidirectional"))
    )
    (net (code "164") (name "unconnected-(U$1-PadNC8-PF4)") (class "Default")
      (node (ref "U$1") (pin "NC8-PF4") (pinfunction "NC8-PF4_NC8-PF4") (pintype "bidirectional"))
    )
    (net (code "165") (name "unconnected-(U$1-PadNRESET)") (class "Default")
      (node (ref "U$1") (pin "NRESET") (pinfunction "NRESET_NRESET") (pintype "input"))
    )
    (net (code "166") (name "unconnected-(U$1-PadPA1)") (class "Default")
      (node (ref "U$1") (pin "PA1") (pinfunction "PA1_PA1") (pintype "bidirectional"))
    )
    (net (code "167") (name "unconnected-(U$1-PadPA2)") (class "Default")
      (node (ref "U$1") (pin "PA2") (pinfunction "PA2_PA2") (pintype "bidirectional"))
    )
    (net (code "168") (name "unconnected-(U$1-PadPA3)") (class "Default")
      (node (ref "U$1") (pin "PA3") (pinfunction "PA3_PA3") (pintype "bidirectional"))
    )
    (net (code "169") (name "unconnected-(U$1-PadPA5)") (class "Default")
      (node (ref "U$1") (pin "PA5") (pinfunction "PA5_PA5") (pintype "bidirectional"))
    )
    (net (code "170") (name "unconnected-(U$1-PadPA7)") (class "Default")
      (node (ref "U$1") (pin "PA7") (pinfunction "PA7_PA7") (pintype "bidirectional"))
    )
    (net (code "171") (name "unconnected-(U$1-PadPA9)") (class "Default")
      (node (ref "U$1") (pin "PA9") (pinfunction "PA9_PA9") (pintype "bidirectional"))
    )
    (net (code "172") (name "unconnected-(U$1-PadPA10)") (class "Default")
      (node (ref "U$1") (pin "PA10") (pinfunction "PA10_PA10") (pintype "bidirectional"))
    )
    (net (code "173") (name "unconnected-(U$1-PadPA11)") (class "Default")
      (node (ref "U$1") (pin "PA11") (pinfunction "PA11_PA11") (pintype "bidirectional"))
    )
    (net (code "174") (name "unconnected-(U$1-PadPA12)") (class "Default")
      (node (ref "U$1") (pin "PA12") (pinfunction "PA12_PA12") (pintype "bidirectional"))
    )
    (net (code "175") (name "unconnected-(U$1-PadPA13)") (class "Default")
      (node (ref "U$1") (pin "PA13") (pinfunction "PA13_PA13") (pintype "bidirectional"))
    )
    (net (code "176") (name "unconnected-(U$1-PadPA14)") (class "Default")
      (node (ref "U$1") (pin "PA14") (pinfunction "PA14_PA14") (pintype "bidirectional"))
    )
    (net (code "177") (name "unconnected-(U$1-PadPB0)") (class "Default")
      (node (ref "U$1") (pin "PB0") (pinfunction "PB0_PB0") (pintype "bidirectional"))
    )
    (net (code "178") (name "unconnected-(U$1-PadPB13)") (class "Default")
      (node (ref "U$1") (pin "PB13") (pinfunction "PB13_PB13") (pintype "bidirectional"))
    )
    (net (code "179") (name "unconnected-(U$1-PadPC1)") (class "Default")
      (node (ref "U$1") (pin "PC1") (pinfunction "PC1_PC1") (pintype "bidirectional"))
    )
    (net (code "180") (name "unconnected-(U$1-PadPC4)") (class "Default")
      (node (ref "U$1") (pin "PC4") (pinfunction "PC4_PC4") (pintype "bidirectional"))
    )
    (net (code "181") (name "unconnected-(U$1-PadPC5)") (class "Default")
      (node (ref "U$1") (pin "PC5") (pinfunction "PC5_PC5") (pintype "bidirectional"))
    )
    (net (code "182") (name "unconnected-(U$1-PadPC13)") (class "Default")
      (node (ref "U$1") (pin "PC13") (pinfunction "PC13_PC13") (pintype "bidirectional"))
    )
    (net (code "183") (name "unconnected-(U$1-PadPC14)") (class "Default")
      (node (ref "U$1") (pin "PC14") (pinfunction "PC14_PC14") (pintype "bidirectional"))
    )
    (net (code "184") (name "unconnected-(U$1-PadPC15)") (class "Default")
      (node (ref "U$1") (pin "PC15") (pinfunction "PC15_PC15") (pintype "bidirectional"))
    )
    (net (code "185") (name "unconnected-(U$1-PadPF0-PH0)") (class "Default")
      (node (ref "U$1") (pin "PF0-PH0") (pinfunction "PF0-PH0_PF0-PH0") (pintype "bidirectional"))
    )
  )
)
